# oboard2.net
KiCad netlist of a schematic drawn in EAGLE
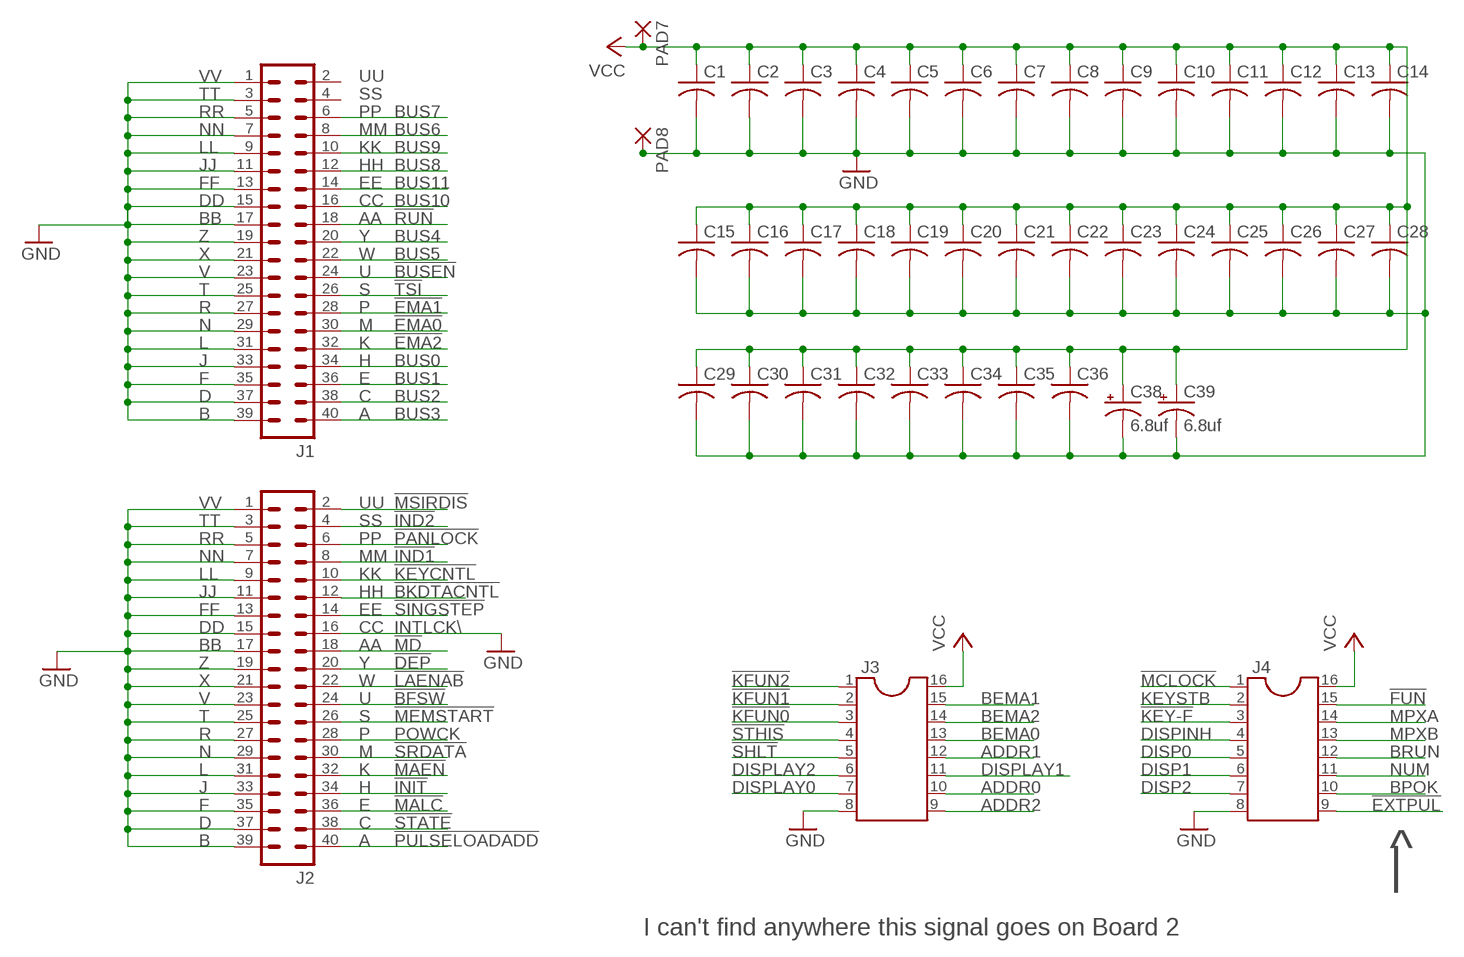
[diagram p0: schematic, sheet 1]
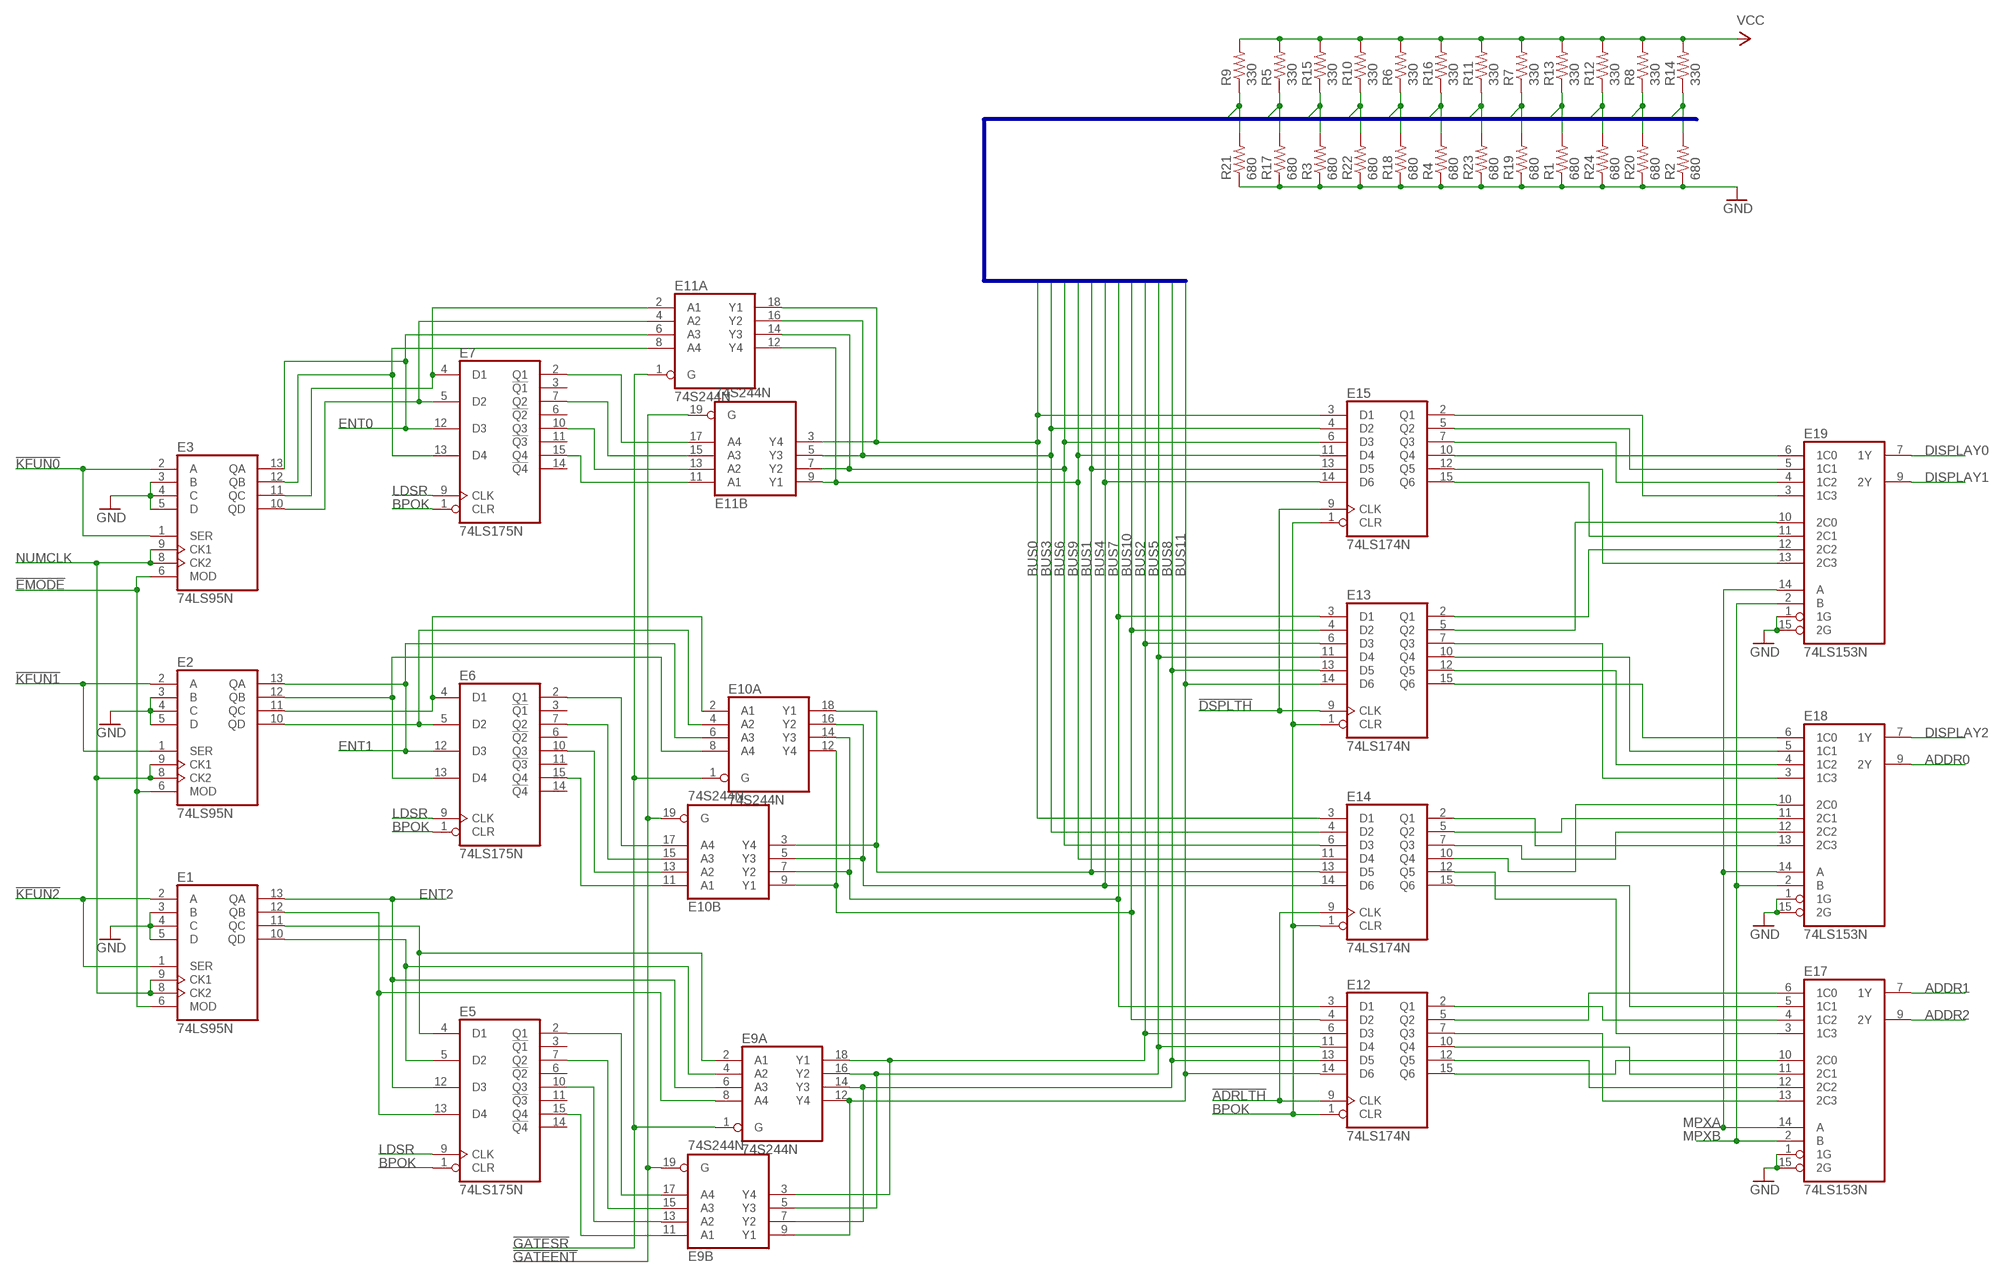
[diagram p1: schematic, sheet 2]
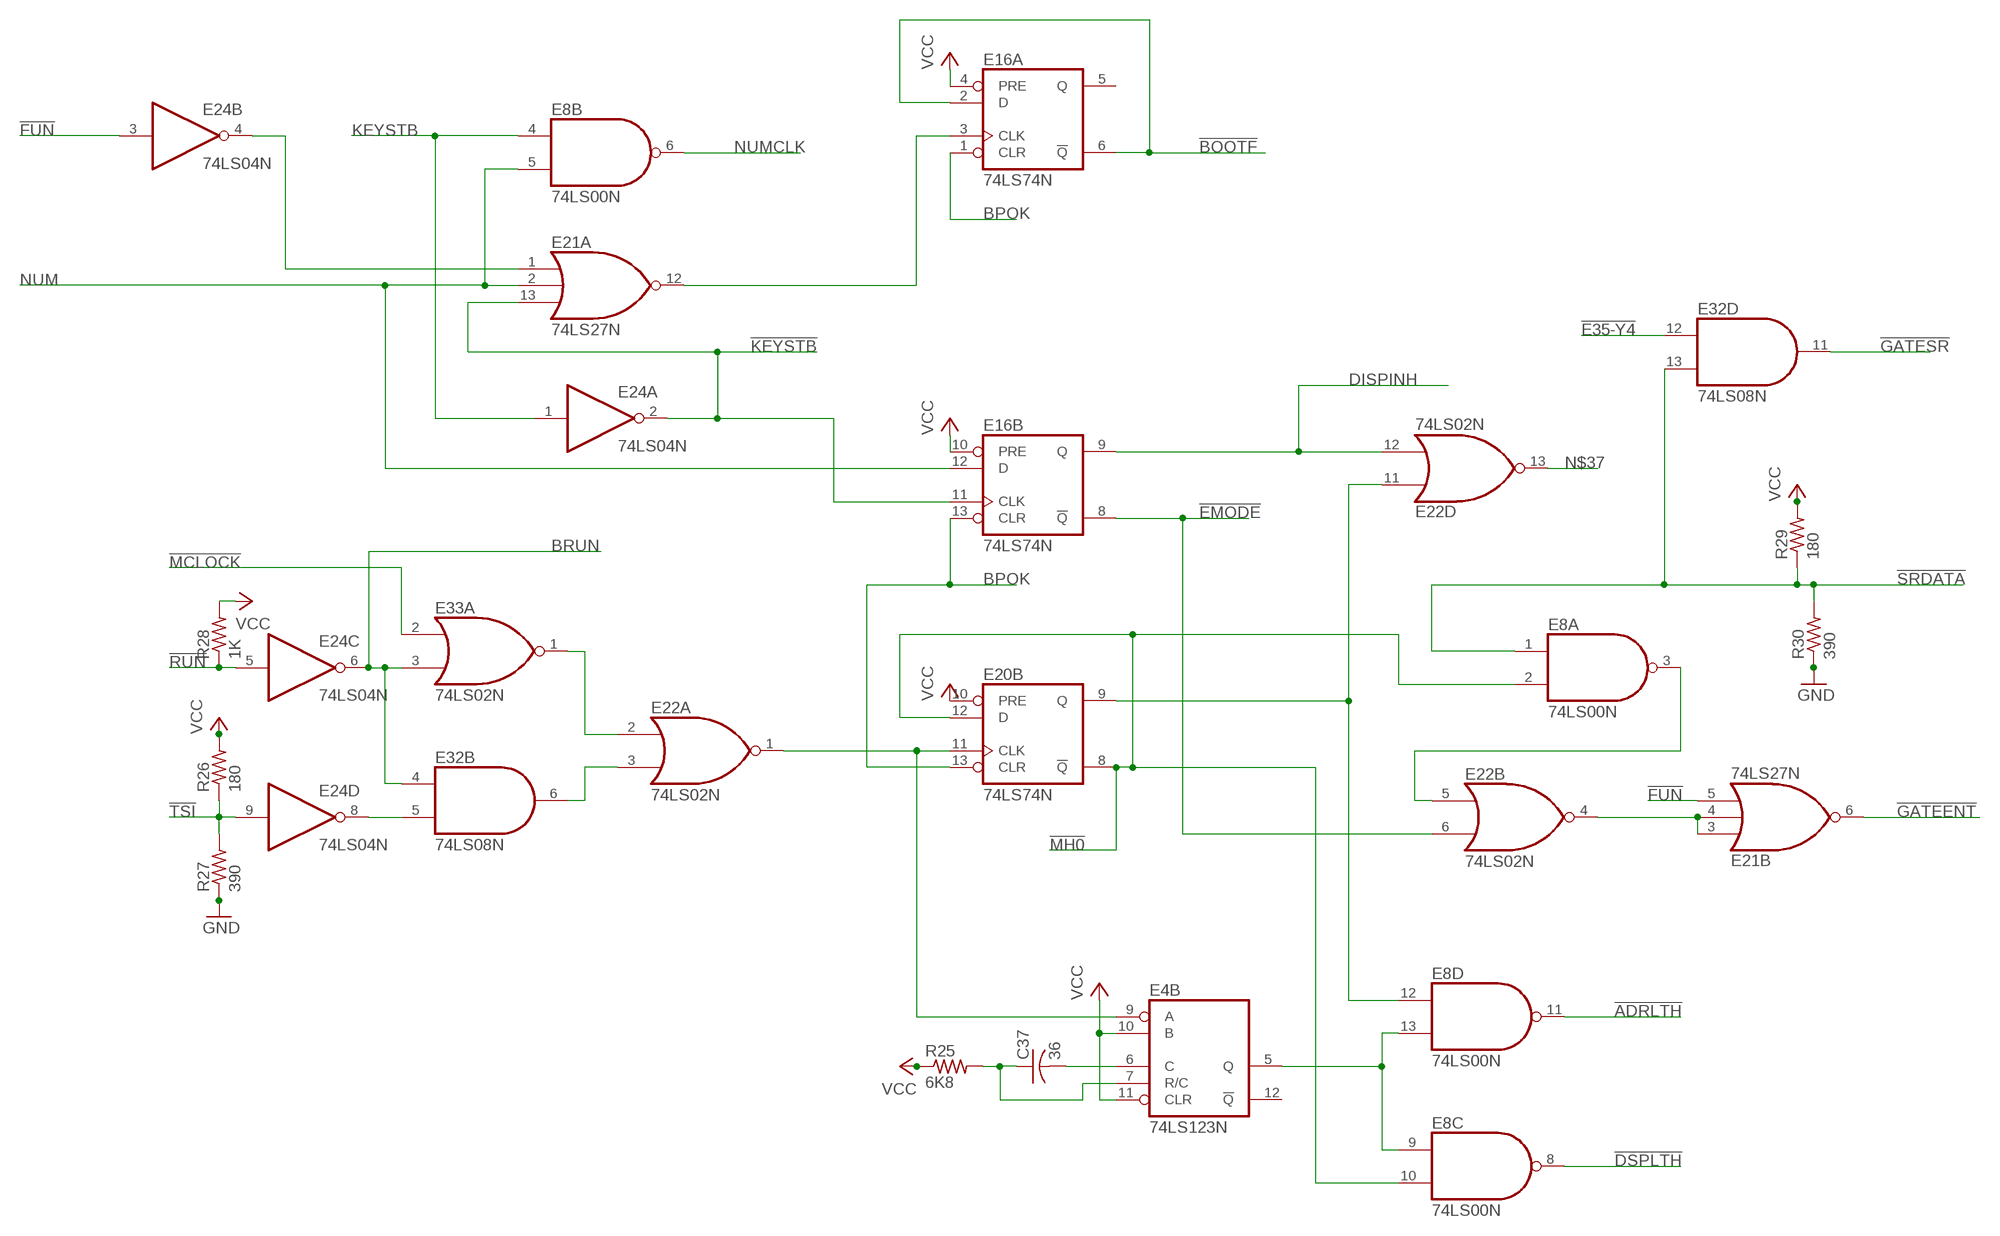
[diagram p2: schematic, sheet 3]
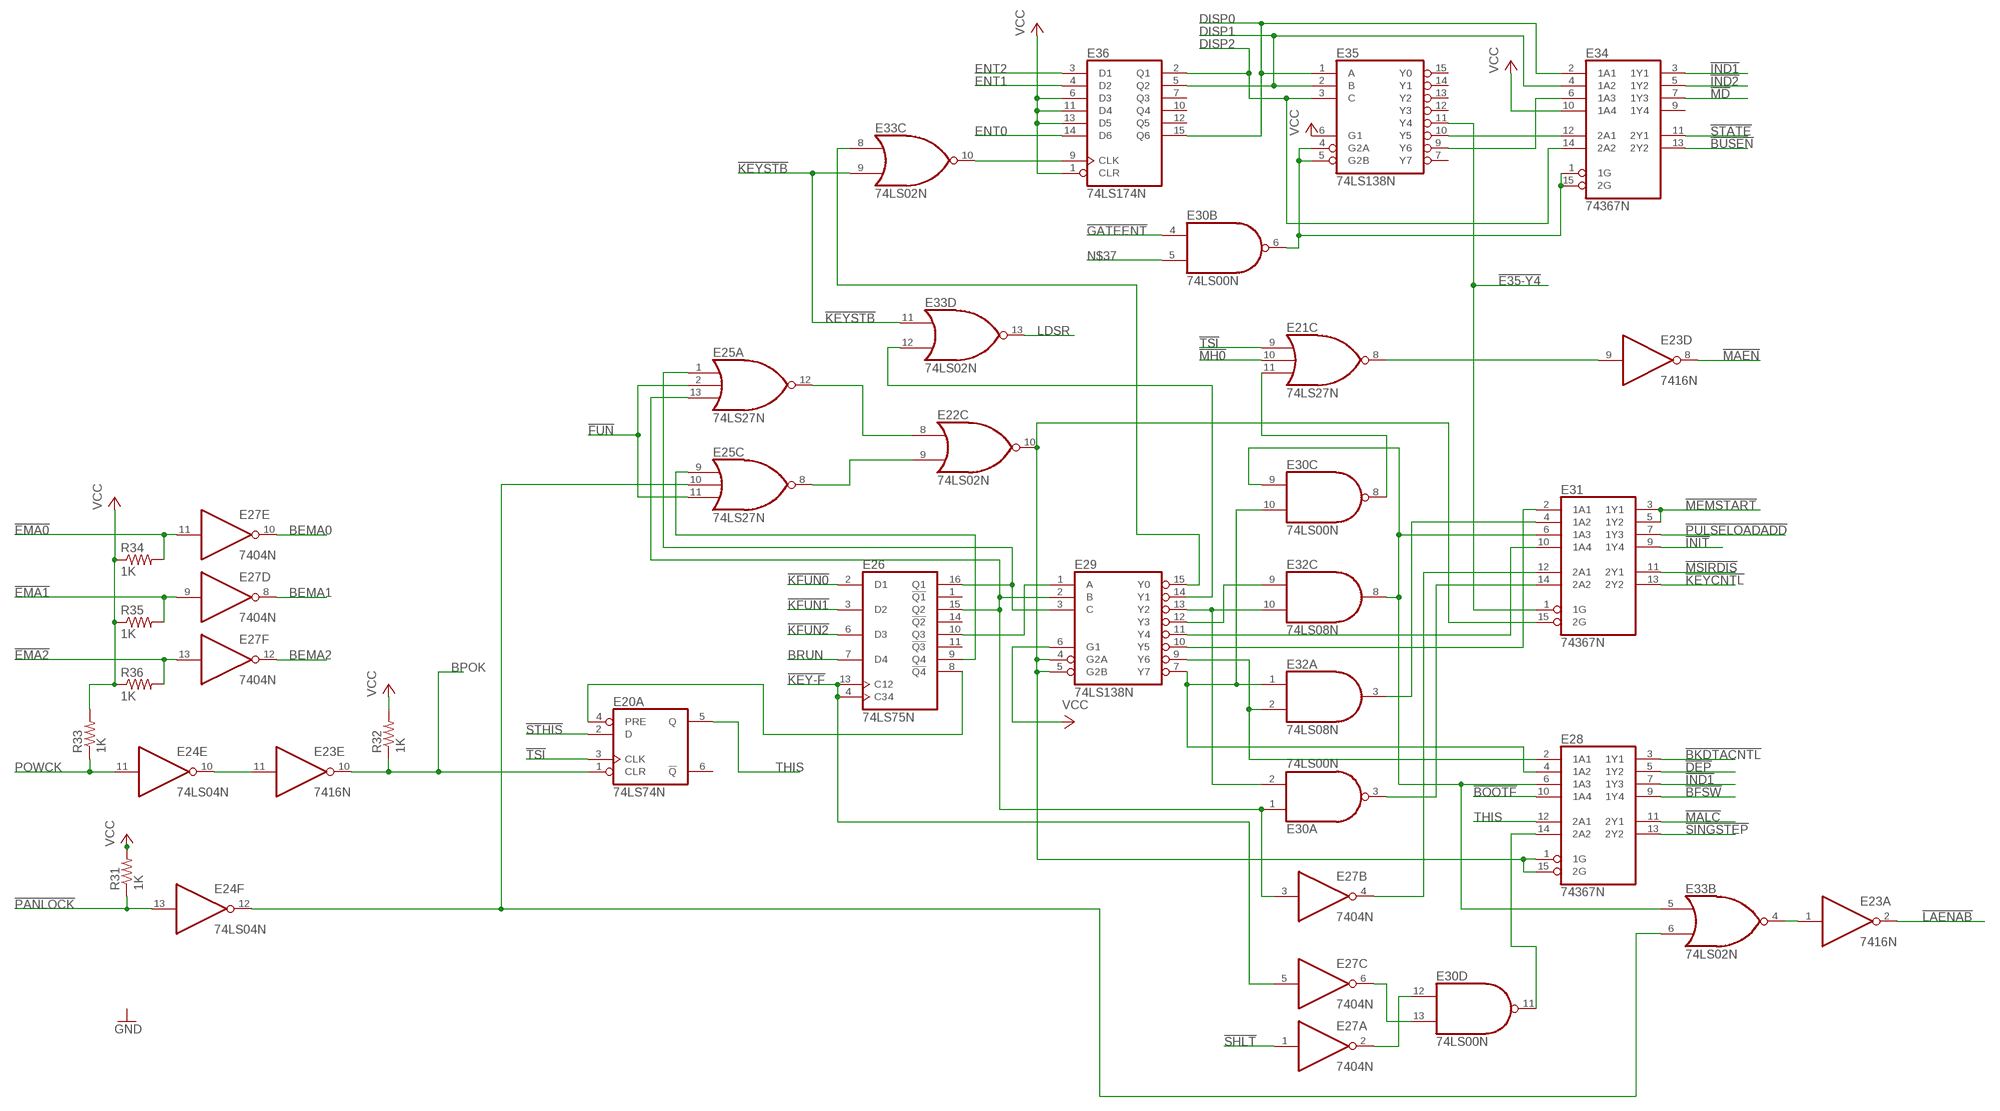
[diagram p3: schematic, sheet 4]

(export (version "E")
  (design (tool "Eeschema 10.0.6"))
  (components
    (comp (ref "E1")
      (value "74LS95N")
      (footprint "eagle-import:DIL14")
      (libsource (lib "eagle-import") (part "7495NLS"))
    )
    (comp (ref "E2")
      (value "74LS95N")
      (footprint "eagle-import:DIL14")
      (libsource (lib "eagle-import") (part "7495NLS"))
    )
    (comp (ref "E3")
      (value "74LS95N")
      (footprint "eagle-import:DIL14")
      (libsource (lib "eagle-import") (part "7495NLS"))
    )
    (comp (ref "E5")
      (value "74LS175N")
      (footprint "eagle-import:DIL16")
      (libsource (lib "eagle-import") (part "74175NLS"))
    )
    (comp (ref "E6")
      (value "74LS175N")
      (footprint "eagle-import:DIL16")
      (libsource (lib "eagle-import") (part "74175NLS"))
    )
    (comp (ref "E7")
      (value "74LS175N")
      (footprint "eagle-import:DIL16")
      (libsource (lib "eagle-import") (part "74175NLS"))
    )
    (comp (ref "E9")
      (value "74S244N")
      (footprint "eagle-import:DIL20")
      (libsource (lib "eagle-import") (part "74244NS"))
    )
    (comp (ref "E10")
      (value "74S244N")
      (footprint "eagle-import:DIL20")
      (libsource (lib "eagle-import") (part "74244NS"))
    )
    (comp (ref "E11")
      (value "74S244N")
      (footprint "eagle-import:DIL20")
      (libsource (lib "eagle-import") (part "74244NS"))
    )
    (comp (ref "E12")
      (value "74LS174N")
      (footprint "eagle-import:DIL16")
      (libsource (lib "eagle-import") (part "74174NLS"))
    )
    (comp (ref "E13")
      (value "74LS174N")
      (footprint "eagle-import:DIL16")
      (libsource (lib "eagle-import") (part "74174NLS"))
    )
    (comp (ref "E14")
      (value "74LS174N")
      (footprint "eagle-import:DIL16")
      (libsource (lib "eagle-import") (part "74174NLS"))
    )
    (comp (ref "E15")
      (value "74LS174N")
      (footprint "eagle-import:DIL16")
      (libsource (lib "eagle-import") (part "74174NLS"))
    )
    (comp (ref "E17")
      (value "74LS153N")
      (footprint "eagle-import:DIL16")
      (libsource (lib "eagle-import") (part "74153NLS"))
    )
    (comp (ref "E18")
      (value "74LS153N")
      (footprint "eagle-import:DIL16")
      (libsource (lib "eagle-import") (part "74153NLS"))
    )
    (comp (ref "E19")
      (value "74LS153N")
      (footprint "eagle-import:DIL16")
      (libsource (lib "eagle-import") (part "74153NLS"))
    )
    (comp (ref "R1")
      (value "680")
      (footprint "eagle-import:0207_10")
      (libsource (lib "eagle-import") (part "R-US_0207/10"))
    )
    (comp (ref "R2")
      (value "680")
      (footprint "eagle-import:0207_10")
      (libsource (lib "eagle-import") (part "R-US_0207/10"))
    )
    (comp (ref "R3")
      (value "680")
      (footprint "eagle-import:0207_10")
      (libsource (lib "eagle-import") (part "R-US_0207/10"))
    )
    (comp (ref "R4")
      (value "680")
      (footprint "eagle-import:0207_10")
      (libsource (lib "eagle-import") (part "R-US_0207/10"))
    )
    (comp (ref "R5")
      (value "330")
      (footprint "eagle-import:0207_10")
      (libsource (lib "eagle-import") (part "R-US_0207/10"))
    )
    (comp (ref "R6")
      (value "330")
      (footprint "eagle-import:0207_10")
      (libsource (lib "eagle-import") (part "R-US_0207/10"))
    )
    (comp (ref "R7")
      (value "330")
      (footprint "eagle-import:0207_10")
      (libsource (lib "eagle-import") (part "R-US_0207/10"))
    )
    (comp (ref "R8")
      (value "330")
      (footprint "eagle-import:0207_10")
      (libsource (lib "eagle-import") (part "R-US_0207/10"))
    )
    (comp (ref "R9")
      (value "330")
      (footprint "eagle-import:0207_10")
      (libsource (lib "eagle-import") (part "R-US_0207/10"))
    )
    (comp (ref "R10")
      (value "330")
      (footprint "eagle-import:0207_10")
      (libsource (lib "eagle-import") (part "R-US_0207/10"))
    )
    (comp (ref "R11")
      (value "330")
      (footprint "eagle-import:0207_10")
      (libsource (lib "eagle-import") (part "R-US_0207/10"))
    )
    (comp (ref "R12")
      (value "330")
      (footprint "eagle-import:0207_10")
      (libsource (lib "eagle-import") (part "R-US_0207/10"))
    )
    (comp (ref "R13")
      (value "330")
      (footprint "eagle-import:0207_10")
      (libsource (lib "eagle-import") (part "R-US_0207/10"))
    )
    (comp (ref "R14")
      (value "330")
      (footprint "eagle-import:0207_10")
      (libsource (lib "eagle-import") (part "R-US_0207/10"))
    )
    (comp (ref "R15")
      (value "330")
      (footprint "eagle-import:0207_10")
      (libsource (lib "eagle-import") (part "R-US_0207/10"))
    )
    (comp (ref "R16")
      (value "330")
      (footprint "eagle-import:0207_10")
      (libsource (lib "eagle-import") (part "R-US_0207/10"))
    )
    (comp (ref "R17")
      (value "680")
      (footprint "eagle-import:0207_10")
      (libsource (lib "eagle-import") (part "R-US_0207/10"))
    )
    (comp (ref "R18")
      (value "680")
      (footprint "eagle-import:0207_10")
      (libsource (lib "eagle-import") (part "R-US_0207/10"))
    )
    (comp (ref "R19")
      (value "680")
      (footprint "eagle-import:0207_10")
      (libsource (lib "eagle-import") (part "R-US_0207/10"))
    )
    (comp (ref "R20")
      (value "680")
      (footprint "eagle-import:0207_10")
      (libsource (lib "eagle-import") (part "R-US_0207/10"))
    )
    (comp (ref "R21")
      (value "680")
      (footprint "eagle-import:0207_10")
      (libsource (lib "eagle-import") (part "R-US_0207/10"))
    )
    (comp (ref "R22")
      (value "680")
      (footprint "eagle-import:0207_10")
      (libsource (lib "eagle-import") (part "R-US_0207/10"))
    )
    (comp (ref "R23")
      (value "680")
      (footprint "eagle-import:0207_10")
      (libsource (lib "eagle-import") (part "R-US_0207/10"))
    )
    (comp (ref "R24")
      (value "680")
      (footprint "eagle-import:0207_10")
      (libsource (lib "eagle-import") (part "R-US_0207/10"))
    )
    (comp (ref "E20")
      (value "74LS74N")
      (footprint "eagle-import:DIL14")
      (libsource (lib "eagle-import") (part "7474NLS"))
    )
    (comp (ref "E21")
      (value "74LS27N")
      (footprint "eagle-import:DIL14")
      (libsource (lib "eagle-import") (part "7427NLS"))
    )
    (comp (ref "E22")
      (value "74LS02N")
      (footprint "eagle-import:DIL14")
      (libsource (lib "eagle-import") (part "7402NLS"))
    )
    (comp (ref "E23")
      (value "7416N")
      (footprint "eagle-import:DIL14")
      (libsource (lib "eagle-import") (part "7416N"))
    )
    (comp (ref "E24")
      (value "74LS04N")
      (footprint "eagle-import:DIL14")
      (libsource (lib "eagle-import") (part "7404NLS"))
    )
    (comp (ref "E25")
      (value "74LS27N")
      (footprint "eagle-import:DIL14")
      (libsource (lib "eagle-import") (part "7427NLS"))
    )
    (comp (ref "E26")
      (value "74LS75N")
      (footprint "eagle-import:DIL16")
      (libsource (lib "eagle-import") (part "7475NLS"))
    )
    (comp (ref "E27")
      (value "7404N")
      (footprint "eagle-import:DIL14")
      (libsource (lib "eagle-import") (part "7404N"))
    )
    (comp (ref "E28")
      (value "74367N")
      (footprint "eagle-import:DIL16")
      (libsource (lib "eagle-import") (part "74367N"))
    )
    (comp (ref "E29")
      (value "74LS138N")
      (footprint "eagle-import:DIL16")
      (libsource (lib "eagle-import") (part "74138NLS"))
    )
    (comp (ref "E30")
      (value "74LS00N")
      (footprint "eagle-import:DIL14")
      (libsource (lib "eagle-import") (part "7400NLS"))
    )
    (comp (ref "E31")
      (value "74367N")
      (footprint "eagle-import:DIL16")
      (libsource (lib "eagle-import") (part "74367N"))
    )
    (comp (ref "E32")
      (value "74LS08N")
      (footprint "eagle-import:DIL14")
      (libsource (lib "eagle-import") (part "7408NLS"))
    )
    (comp (ref "E33")
      (value "74LS02N")
      (footprint "eagle-import:DIL14")
      (libsource (lib "eagle-import") (part "7402NLS"))
    )
    (comp (ref "E34")
      (value "74367N")
      (footprint "eagle-import:DIL16")
      (libsource (lib "eagle-import") (part "74367N"))
    )
    (comp (ref "E35")
      (value "74LS138N")
      (footprint "eagle-import:DIL16")
      (libsource (lib "eagle-import") (part "74138NLS"))
    )
    (comp (ref "E36")
      (value "74LS174N")
      (footprint "eagle-import:DIL16")
      (libsource (lib "eagle-import") (part "74174NLS"))
    )
    (comp (ref "R31")
      (value "1K")
      (footprint "eagle-import:0207_10")
      (libsource (lib "eagle-import") (part "R-US_0207/10"))
    )
    (comp (ref "R32")
      (value "1K")
      (footprint "eagle-import:0207_10")
      (libsource (lib "eagle-import") (part "R-US_0207/10"))
    )
    (comp (ref "R33")
      (value "1K")
      (footprint "eagle-import:0207_10")
      (libsource (lib "eagle-import") (part "R-US_0207/10"))
    )
    (comp (ref "R34")
      (value "1K")
      (footprint "eagle-import:0207_10")
      (libsource (lib "eagle-import") (part "R-US_0207/10"))
    )
    (comp (ref "R35")
      (value "1K")
      (footprint "eagle-import:0207_10")
      (libsource (lib "eagle-import") (part "R-US_0207/10"))
    )
    (comp (ref "R36")
      (value "1K")
      (footprint "eagle-import:0207_10")
      (libsource (lib "eagle-import") (part "R-US_0207/10"))
    )
    (comp (ref "C37")
      (value "36")
      (footprint "eagle-import:C050-025X075")
      (libsource (lib "eagle-import") (part "C-US050-025X075"))
    )
    (comp (ref "E4")
      (value "74LS123N")
      (footprint "eagle-import:DIL16")
      (libsource (lib "eagle-import") (part "74123NLS"))
    )
    (comp (ref "E8")
      (value "74LS00N")
      (footprint "eagle-import:DIL14")
      (libsource (lib "eagle-import") (part "7400NLS"))
    )
    (comp (ref "E16")
      (value "74LS74N")
      (footprint "eagle-import:DIL14")
      (libsource (lib "eagle-import") (part "7474NLS"))
    )
    (comp (ref "R25")
      (value "6K8")
      (footprint "eagle-import:0207_10")
      (libsource (lib "eagle-import") (part "R-US_0207/10"))
    )
    (comp (ref "R26")
      (value "180")
      (footprint "eagle-import:0207_10")
      (libsource (lib "eagle-import") (part "R-US_0207/10"))
    )
    (comp (ref "R27")
      (value "390")
      (footprint "eagle-import:0207_10")
      (libsource (lib "eagle-import") (part "R-US_0207/10"))
    )
    (comp (ref "R28")
      (value "1K")
      (footprint "eagle-import:0207_10")
      (libsource (lib "eagle-import") (part "R-US_0207/10"))
    )
    (comp (ref "R29")
      (value "180")
      (footprint "eagle-import:0207_10")
      (libsource (lib "eagle-import") (part "R-US_0207/10"))
    )
    (comp (ref "R30")
      (value "390")
      (footprint "eagle-import:0207_10")
      (libsource (lib "eagle-import") (part "R-US_0207/10"))
    )
    (comp (ref "C1")
      (value "C-US050-025X075")
      (footprint "eagle-import:C050-025X075")
      (libsource (lib "eagle-import") (part "C-US050-025X075"))
    )
    (comp (ref "C2")
      (value "C-US050-025X075")
      (footprint "eagle-import:C050-025X075")
      (libsource (lib "eagle-import") (part "C-US050-025X075"))
    )
    (comp (ref "C3")
      (value "C-US050-025X075")
      (footprint "eagle-import:C050-025X075")
      (libsource (lib "eagle-import") (part "C-US050-025X075"))
    )
    (comp (ref "C4")
      (value "C-US050-025X075")
      (footprint "eagle-import:C050-025X075")
      (libsource (lib "eagle-import") (part "C-US050-025X075"))
    )
    (comp (ref "C5")
      (value "C-US050-025X075")
      (footprint "eagle-import:C050-025X075")
      (libsource (lib "eagle-import") (part "C-US050-025X075"))
    )
    (comp (ref "C6")
      (value "C-US050-025X075")
      (footprint "eagle-import:C050-025X075")
      (libsource (lib "eagle-import") (part "C-US050-025X075"))
    )
    (comp (ref "C7")
      (value "C-US050-025X075")
      (footprint "eagle-import:C050-025X075")
      (libsource (lib "eagle-import") (part "C-US050-025X075"))
    )
    (comp (ref "C8")
      (value "C-US050-025X075")
      (footprint "eagle-import:C050-025X075")
      (libsource (lib "eagle-import") (part "C-US050-025X075"))
    )
    (comp (ref "C9")
      (value "C-US050-025X075")
      (footprint "eagle-import:C050-025X075")
      (libsource (lib "eagle-import") (part "C-US050-025X075"))
    )
    (comp (ref "C10")
      (value "C-US050-025X075")
      (footprint "eagle-import:C050-025X075")
      (libsource (lib "eagle-import") (part "C-US050-025X075"))
    )
    (comp (ref "C11")
      (value "C-US050-025X075")
      (footprint "eagle-import:C050-025X075")
      (libsource (lib "eagle-import") (part "C-US050-025X075"))
    )
    (comp (ref "C12")
      (value "C-US050-025X075")
      (footprint "eagle-import:C050-025X075")
      (libsource (lib "eagle-import") (part "C-US050-025X075"))
    )
    (comp (ref "C13")
      (value "C-US050-025X075")
      (footprint "eagle-import:C050-025X075")
      (libsource (lib "eagle-import") (part "C-US050-025X075"))
    )
    (comp (ref "C14")
      (value "C-US050-025X075")
      (footprint "eagle-import:C050-025X075")
      (libsource (lib "eagle-import") (part "C-US050-025X075"))
    )
    (comp (ref "C15")
      (value "C-US050-025X075")
      (footprint "eagle-import:C050-025X075")
      (libsource (lib "eagle-import") (part "C-US050-025X075"))
    )
    (comp (ref "C16")
      (value "C-US050-025X075")
      (footprint "eagle-import:C050-025X075")
      (libsource (lib "eagle-import") (part "C-US050-025X075"))
    )
    (comp (ref "C17")
      (value "C-US050-025X075")
      (footprint "eagle-import:C050-025X075")
      (libsource (lib "eagle-import") (part "C-US050-025X075"))
    )
    (comp (ref "C18")
      (value "C-US050-025X075")
      (footprint "eagle-import:C050-025X075")
      (libsource (lib "eagle-import") (part "C-US050-025X075"))
    )
    (comp (ref "C19")
      (value "C-US050-025X075")
      (footprint "eagle-import:C050-025X075")
      (libsource (lib "eagle-import") (part "C-US050-025X075"))
    )
    (comp (ref "C20")
      (value "C-US050-025X075")
      (footprint "eagle-import:C050-025X075")
      (libsource (lib "eagle-import") (part "C-US050-025X075"))
    )
    (comp (ref "C21")
      (value "C-US050-025X075")
      (footprint "eagle-import:C050-025X075")
      (libsource (lib "eagle-import") (part "C-US050-025X075"))
    )
    (comp (ref "C22")
      (value "C-US050-025X075")
      (footprint "eagle-import:C050-025X075")
      (libsource (lib "eagle-import") (part "C-US050-025X075"))
    )
    (comp (ref "C23")
      (value "C-US050-025X075")
      (footprint "eagle-import:C050-025X075")
      (libsource (lib "eagle-import") (part "C-US050-025X075"))
    )
    (comp (ref "C24")
      (value "C-US050-025X075")
      (footprint "eagle-import:C050-025X075")
      (libsource (lib "eagle-import") (part "C-US050-025X075"))
    )
    (comp (ref "C25")
      (value "C-US050-025X075")
      (footprint "eagle-import:C050-025X075")
      (libsource (lib "eagle-import") (part "C-US050-025X075"))
    )
    (comp (ref "C26")
      (value "C-US050-025X075")
      (footprint "eagle-import:C050-025X075")
      (libsource (lib "eagle-import") (part "C-US050-025X075"))
    )
    (comp (ref "C27")
      (value "C-US050-025X075")
      (footprint "eagle-import:C050-025X075")
      (libsource (lib "eagle-import") (part "C-US050-025X075"))
    )
    (comp (ref "C28")
      (value "C-US050-025X075")
      (footprint "eagle-import:C050-025X075")
      (libsource (lib "eagle-import") (part "C-US050-025X075"))
    )
    (comp (ref "C29")
      (value "C-US050-025X075")
      (footprint "eagle-import:C050-025X075")
      (libsource (lib "eagle-import") (part "C-US050-025X075"))
    )
    (comp (ref "C30")
      (value "C-US050-025X075")
      (footprint "eagle-import:C050-025X075")
      (libsource (lib "eagle-import") (part "C-US050-025X075"))
    )
    (comp (ref "C31")
      (value "C-US050-025X075")
      (footprint "eagle-import:C050-025X075")
      (libsource (lib "eagle-import") (part "C-US050-025X075"))
    )
    (comp (ref "C32")
      (value "C-US050-025X075")
      (footprint "eagle-import:C050-025X075")
      (libsource (lib "eagle-import") (part "C-US050-025X075"))
    )
    (comp (ref "C33")
      (value "C-US050-025X075")
      (footprint "eagle-import:C050-025X075")
      (libsource (lib "eagle-import") (part "C-US050-025X075"))
    )
    (comp (ref "C34")
      (value "C-US050-025X075")
      (footprint "eagle-import:C050-025X075")
      (libsource (lib "eagle-import") (part "C-US050-025X075"))
    )
    (comp (ref "C35")
      (value "C-US050-025X075")
      (footprint "eagle-import:C050-025X075")
      (libsource (lib "eagle-import") (part "C-US050-025X075"))
    )
    (comp (ref "C36")
      (value "C-US050-025X075")
      (footprint "eagle-import:C050-025X075")
      (libsource (lib "eagle-import") (part "C-US050-025X075"))
    )
    (comp (ref "C38")
      (value "6.8uf")
      (footprint "eagle-import:E15-5")
      (libsource (lib "eagle-import") (part "CPOL-USE15-5AXIAL"))
    )
    (comp (ref "C39")
      (value "6.8uf")
      (footprint "eagle-import:E15-5")
      (libsource (lib "eagle-import") (part "CPOL-USE15-5AXIAL"))
    )
    (comp (ref "J1")
      (value "40H")
      (footprint "eagle-import:40H")
      (libsource (lib "eagle-import") (part "40H"))
    )
    (comp (ref "J2")
      (value "40H")
      (footprint "eagle-import:40H")
      (libsource (lib "eagle-import") (part "40H"))
    )
    (comp (ref "J3")
      (value "DIL16S")
      (footprint "eagle-import:SOCKET-16")
      (libsource (lib "eagle-import") (part "DIL16S"))
    )
    (comp (ref "J4")
      (value "DIL16S")
      (footprint "eagle-import:SOCKET-16")
      (libsource (lib "eagle-import") (part "DIL16S"))
    )
    (comp (ref "PAD7")
      (value "3,81/1,4")
      (footprint "eagle-import:3,81_1,4")
      (libsource (lib "eagle-import") (part "3,81/1,4"))
    )
    (comp (ref "PAD8")
      (value "3,81/1,4")
      (footprint "eagle-import:3,81_1,4")
      (libsource (lib "eagle-import") (part "3,81/1,4"))
    )
  )
  (nets
    (net (code "1") (name "ADDR0") (class "Default")
      (node (ref "E18") (pin "9") (pinfunction "2Y_9") (pintype "output"))
      (node (ref "J3") (pin "10") (pinfunction "10_10") (pintype "passive"))
    )
    (net (code "2") (name "ADDR1") (class "Default")
      (node (ref "E17") (pin "7") (pinfunction "1Y_7") (pintype "output"))
      (node (ref "J3") (pin "12") (pinfunction "12_12") (pintype "passive"))
    )
    (net (code "3") (name "ADDR2") (class "Default")
      (node (ref "E17") (pin "9") (pinfunction "2Y_9") (pintype "output"))
      (node (ref "J3") (pin "9") (pinfunction "9_9") (pintype "passive"))
    )
    (net (code "4") (name "BEMA0") (class "Default")
      (node (ref "E27") (pin "10") (pinfunction "O_10") (pintype "output"))
      (node (ref "J3") (pin "13") (pinfunction "13_13") (pintype "passive"))
    )
    (net (code "5") (name "BEMA1") (class "Default")
      (node (ref "E27") (pin "8") (pinfunction "O_8") (pintype "output"))
      (node (ref "J3") (pin "15") (pinfunction "15_15") (pintype "passive"))
    )
    (net (code "6") (name "BEMA2") (class "Default")
      (node (ref "E27") (pin "12") (pinfunction "O_12") (pintype "output"))
      (node (ref "J3") (pin "14") (pinfunction "14_14") (pintype "passive"))
    )
    (net (code "7") (name "BPOK") (class "Default")
      (node (ref "E12") (pin "1") (pinfunction "CLR_1") (pintype "input"))
      (node (ref "E13") (pin "1") (pinfunction "CLR_1") (pintype "input"))
      (node (ref "E14") (pin "1") (pinfunction "CLR_1") (pintype "input"))
      (node (ref "E15") (pin "1") (pinfunction "CLR_1") (pintype "input"))
      (node (ref "E16") (pin "1") (pinfunction "CLR_1") (pintype "input"))
      (node (ref "E16") (pin "13") (pinfunction "CLR_13") (pintype "input"))
      (node (ref "E20") (pin "1") (pinfunction "CLR_1") (pintype "input"))
      (node (ref "E20") (pin "13") (pinfunction "CLR_13") (pintype "input"))
      (node (ref "E23") (pin "10") (pinfunction "O_10") (pintype "open_collector"))
      (node (ref "E5") (pin "1") (pinfunction "CLR_1") (pintype "input"))
      (node (ref "E6") (pin "1") (pinfunction "CLR_1") (pintype "input"))
      (node (ref "E7") (pin "1") (pinfunction "CLR_1") (pintype "input"))
      (node (ref "J4") (pin "10") (pinfunction "10_10") (pintype "passive"))
      (node (ref "R32") (pin "1") (pinfunction "1_1") (pintype "passive"))
    )
    (net (code "8") (name "BRUN") (class "Default")
      (node (ref "E24") (pin "6") (pinfunction "O_6") (pintype "output"))
      (node (ref "E26") (pin "7") (pinfunction "D4_7") (pintype "input"))
      (node (ref "E32") (pin "4") (pinfunction "I0_4") (pintype "input"))
      (node (ref "E33") (pin "3") (pinfunction "I1_3") (pintype "input"))
      (node (ref "J4") (pin "12") (pinfunction "12_12") (pintype "passive"))
    )
    (net (code "9") (name "BUS0") (class "Default")
      (node (ref "E11") (pin "18") (pinfunction "Y1_18") (pintype "tri_state"))
      (node (ref "E11") (pin "3") (pinfunction "Y4_3") (pintype "tri_state"))
      (node (ref "E14") (pin "3") (pinfunction "D1_3") (pintype "input"))
      (node (ref "E15") (pin "3") (pinfunction "D1_3") (pintype "input"))
      (node (ref "J1") (pin "34") (pinfunction "34_34") (pintype "passive"))
      (node (ref "R21") (pin "2") (pinfunction "2_2") (pintype "passive"))
      (node (ref "R9") (pin "1") (pinfunction "1_1") (pintype "passive"))
    )
    (net (code "10") (name "BUS1") (class "Default")
      (node (ref "E10") (pin "18") (pinfunction "Y1_18") (pintype "tri_state"))
      (node (ref "E10") (pin "3") (pinfunction "Y4_3") (pintype "tri_state"))
      (node (ref "E14") (pin "13") (pinfunction "D5_13") (pintype "input"))
      (node (ref "E15") (pin "13") (pinfunction "D5_13") (pintype "input"))
      (node (ref "J1") (pin "36") (pinfunction "36_36") (pintype "passive"))
      (node (ref "R17") (pin "2") (pinfunction "2_2") (pintype "passive"))
      (node (ref "R5") (pin "1") (pinfunction "1_1") (pintype "passive"))
    )
    (net (code "11") (name "BUS2") (class "Default")
      (node (ref "E12") (pin "6") (pinfunction "D3_6") (pintype "input"))
      (node (ref "E13") (pin "6") (pinfunction "D3_6") (pintype "input"))
      (node (ref "E9") (pin "18") (pinfunction "Y1_18") (pintype "tri_state"))
      (node (ref "E9") (pin "3") (pinfunction "Y4_3") (pintype "tri_state"))
      (node (ref "J1") (pin "38") (pinfunction "38_38") (pintype "passive"))
      (node (ref "R15") (pin "1") (pinfunction "1_1") (pintype "passive"))
      (node (ref "R3") (pin "2") (pinfunction "2_2") (pintype "passive"))
    )
    (net (code "12") (name "BUS3") (class "Default")
      (node (ref "E11") (pin "16") (pinfunction "Y2_16") (pintype "tri_state"))
      (node (ref "E11") (pin "5") (pinfunction "Y3_5") (pintype "tri_state"))
      (node (ref "E14") (pin "4") (pinfunction "D2_4") (pintype "input"))
      (node (ref "E15") (pin "4") (pinfunction "D2_4") (pintype "input"))
      (node (ref "J1") (pin "40") (pinfunction "40_40") (pintype "passive"))
      (node (ref "R10") (pin "1") (pinfunction "1_1") (pintype "passive"))
      (node (ref "R22") (pin "2") (pinfunction "2_2") (pintype "passive"))
    )
    (net (code "13") (name "BUS4") (class "Default")
      (node (ref "E10") (pin "16") (pinfunction "Y2_16") (pintype "tri_state"))
      (node (ref "E10") (pin "5") (pinfunction "Y3_5") (pintype "tri_state"))
      (node (ref "E14") (pin "14") (pinfunction "D6_14") (pintype "input"))
      (node (ref "E15") (pin "14") (pinfunction "D6_14") (pintype "input"))
      (node (ref "J1") (pin "20") (pinfunction "20_20") (pintype "passive"))
      (node (ref "R18") (pin "2") (pinfunction "2_2") (pintype "passive"))
      (node (ref "R6") (pin "1") (pinfunction "1_1") (pintype "passive"))
    )
    (net (code "14") (name "BUS5") (class "Default")
      (node (ref "E12") (pin "11") (pinfunction "D4_11") (pintype "input"))
      (node (ref "E13") (pin "11") (pinfunction "D4_11") (pintype "input"))
      (node (ref "E9") (pin "16") (pinfunction "Y2_16") (pintype "tri_state"))
      (node (ref "E9") (pin "5") (pinfunction "Y3_5") (pintype "tri_state"))
      (node (ref "J1") (pin "22") (pinfunction "22_22") (pintype "passive"))
      (node (ref "R16") (pin "1") (pinfunction "1_1") (pintype "passive"))
      (node (ref "R4") (pin "2") (pinfunction "2_2") (pintype "passive"))
    )
    (net (code "15") (name "BUS6") (class "Default")
      (node (ref "E11") (pin "14") (pinfunction "Y3_14") (pintype "tri_state"))
      (node (ref "E11") (pin "7") (pinfunction "Y2_7") (pintype "tri_state"))
      (node (ref "E14") (pin "6") (pinfunction "D3_6") (pintype "input"))
      (node (ref "E15") (pin "6") (pinfunction "D3_6") (pintype "input"))
      (node (ref "J1") (pin "8") (pinfunction "8_8") (pintype "passive"))
      (node (ref "R11") (pin "1") (pinfunction "1_1") (pintype "passive"))
      (node (ref "R23") (pin "2") (pinfunction "2_2") (pintype "passive"))
    )
    (net (code "16") (name "BUS7") (class "Default")
      (node (ref "E10") (pin "14") (pinfunction "Y3_14") (pintype "tri_state"))
      (node (ref "E10") (pin "7") (pinfunction "Y2_7") (pintype "tri_state"))
      (node (ref "E12") (pin "3") (pinfunction "D1_3") (pintype "input"))
      (node (ref "E13") (pin "3") (pinfunction "D1_3") (pintype "input"))
      (node (ref "J1") (pin "6") (pinfunction "6_6") (pintype "passive"))
      (node (ref "R19") (pin "2") (pinfunction "2_2") (pintype "passive"))
      (node (ref "R7") (pin "1") (pinfunction "1_1") (pintype "passive"))
    )
    (net (code "17") (name "BUS8") (class "Default")
      (node (ref "E12") (pin "13") (pinfunction "D5_13") (pintype "input"))
      (node (ref "E13") (pin "13") (pinfunction "D5_13") (pintype "input"))
      (node (ref "E9") (pin "14") (pinfunction "Y3_14") (pintype "tri_state"))
      (node (ref "E9") (pin "7") (pinfunction "Y2_7") (pintype "tri_state"))
      (node (ref "J1") (pin "12") (pinfunction "12_12") (pintype "passive"))
      (node (ref "R1") (pin "2") (pinfunction "2_2") (pintype "passive"))
      (node (ref "R12") (pin "1") (pinfunction "1_1") (pintype "passive"))
      (node (ref "R13") (pin "1") (pinfunction "1_1") (pintype "passive"))
      (node (ref "R24") (pin "2") (pinfunction "2_2") (pintype "passive"))
    )
    (net (code "18") (name "BUS9") (class "Default")
      (node (ref "E11") (pin "12") (pinfunction "Y4_12") (pintype "tri_state"))
      (node (ref "E11") (pin "9") (pinfunction "Y1_9") (pintype "tri_state"))
      (node (ref "E14") (pin "11") (pinfunction "D4_11") (pintype "input"))
      (node (ref "E15") (pin "11") (pinfunction "D4_11") (pintype "input"))
      (node (ref "J1") (pin "10") (pinfunction "10_10") (pintype "passive"))
    )
    (net (code "19") (name "BUS10") (class "Default")
      (node (ref "E10") (pin "12") (pinfunction "Y4_12") (pintype "tri_state"))
      (node (ref "E10") (pin "9") (pinfunction "Y1_9") (pintype "tri_state"))
      (node (ref "E12") (pin "4") (pinfunction "D2_4") (pintype "input"))
      (node (ref "E13") (pin "4") (pinfunction "D2_4") (pintype "input"))
      (node (ref "J1") (pin "16") (pinfunction "16_16") (pintype "passive"))
      (node (ref "R20") (pin "2") (pinfunction "2_2") (pintype "passive"))
      (node (ref "R8") (pin "1") (pinfunction "1_1") (pintype "passive"))
    )
    (net (code "20") (name "BUS11") (class "Default")
      (node (ref "E12") (pin "14") (pinfunction "D6_14") (pintype "input"))
      (node (ref "E13") (pin "14") (pinfunction "D6_14") (pintype "input"))
      (node (ref "E9") (pin "12") (pinfunction "Y4_12") (pintype "tri_state"))
      (node (ref "E9") (pin "9") (pinfunction "Y1_9") (pintype "tri_state"))
      (node (ref "J1") (pin "14") (pinfunction "14_14") (pintype "passive"))
      (node (ref "R14") (pin "1") (pinfunction "1_1") (pintype "passive"))
      (node (ref "R2") (pin "2") (pinfunction "2_2") (pintype "passive"))
    )
    (net (code "21") (name "DISP0") (class "Default")
      (node (ref "E34") (pin "2") (pinfunction "1A1_2") (pintype "input"))
      (node (ref "E35") (pin "1") (pinfunction "A_1") (pintype "input"))
      (node (ref "E36") (pin "15") (pinfunction "Q6_15") (pintype "output"))
      (node (ref "J4") (pin "5") (pinfunction "5_5") (pintype "passive"))
    )
    (net (code "22") (name "DISP1") (class "Default")
      (node (ref "E34") (pin "4") (pinfunction "1A2_4") (pintype "input"))
      (node (ref "E35") (pin "2") (pinfunction "B_2") (pintype "input"))
      (node (ref "E36") (pin "5") (pinfunction "Q2_5") (pintype "output"))
      (node (ref "J4") (pin "6") (pinfunction "6_6") (pintype "passive"))
    )
    (net (code "23") (name "DISP2") (class "Default")
      (node (ref "E34") (pin "14") (pinfunction "2A2_14") (pintype "input"))
      (node (ref "E35") (pin "3") (pinfunction "C_3") (pintype "input"))
      (node (ref "E36") (pin "2") (pinfunction "Q1_2") (pintype "output"))
      (node (ref "J4") (pin "7") (pinfunction "7_7") (pintype "passive"))
    )
    (net (code "24") (name "DISPINH") (class "Default")
      (node (ref "E16") (pin "9") (pinfunction "Q_9") (pintype "output"))
      (node (ref "E22") (pin "12") (pinfunction "I1_12") (pintype "input"))
      (node (ref "J4") (pin "4") (pinfunction "4_4") (pintype "passive"))
    )
    (net (code "25") (name "DISPLAY0") (class "Default")
      (node (ref "E19") (pin "7") (pinfunction "1Y_7") (pintype "output"))
      (node (ref "J3") (pin "7") (pinfunction "7_7") (pintype "passive"))
    )
    (net (code "26") (name "DISPLAY1") (class "Default")
      (node (ref "E19") (pin "9") (pinfunction "2Y_9") (pintype "output"))
      (node (ref "J3") (pin "11") (pinfunction "11_11") (pintype "passive"))
    )
    (net (code "27") (name "DISPLAY2") (class "Default")
      (node (ref "E18") (pin "7") (pinfunction "1Y_7") (pintype "output"))
      (node (ref "J3") (pin "6") (pinfunction "6_6") (pintype "passive"))
    )
    (net (code "28") (name "ENT0") (class "Default")
      (node (ref "E11") (pin "6") (pinfunction "A3_6") (pintype "input"))
      (node (ref "E3") (pin "13") (pinfunction "QA_13") (pintype "output"))
      (node (ref "E36") (pin "14") (pinfunction "D6_14") (pintype "input"))
      (node (ref "E7") (pin "12") (pinfunction "D3_12") (pintype "input"))
    )
    (net (code "29") (name "ENT1") (class "Default")
      (node (ref "E10") (pin "6") (pinfunction "A3_6") (pintype "input"))
      (node (ref "E2") (pin "13") (pinfunction "QA_13") (pintype "output"))
      (node (ref "E36") (pin "4") (pinfunction "D2_4") (pintype "input"))
      (node (ref "E6") (pin "12") (pinfunction "D3_12") (pintype "input"))
    )
    (net (code "30") (name "ENT2") (class "Default")
      (node (ref "E1") (pin "13") (pinfunction "QA_13") (pintype "output"))
      (node (ref "E36") (pin "3") (pinfunction "D1_3") (pintype "input"))
      (node (ref "E5") (pin "12") (pinfunction "D3_12") (pintype "input"))
      (node (ref "E9") (pin "6") (pinfunction "A3_6") (pintype "input"))
    )
    (net (code "31") (name "GND") (class "Default")
      (node (ref "C1") (pin "2") (pinfunction "2_2") (pintype "passive"))
      (node (ref "C10") (pin "2") (pinfunction "2_2") (pintype "passive"))
      (node (ref "C11") (pin "2") (pinfunction "2_2") (pintype "passive"))
      (node (ref "C12") (pin "2") (pinfunction "2_2") (pintype "passive"))
      (node (ref "C13") (pin "2") (pinfunction "2_2") (pintype "passive"))
      (node (ref "C14") (pin "2") (pinfunction "2_2") (pintype "passive"))
      (node (ref "C15") (pin "2") (pinfunction "2_2") (pintype "passive"))
      (node (ref "C16") (pin "2") (pinfunction "2_2") (pintype "passive"))
      (node (ref "C17") (pin "2") (pinfunction "2_2") (pintype "passive"))
      (node (ref "C18") (pin "2") (pinfunction "2_2") (pintype "passive"))
      (node (ref "C19") (pin "2") (pinfunction "2_2") (pintype "passive"))
      (node (ref "C2") (pin "2") (pinfunction "2_2") (pintype "passive"))
      (node (ref "C20") (pin "2") (pinfunction "2_2") (pintype "passive"))
      (node (ref "C21") (pin "2") (pinfunction "2_2") (pintype "passive"))
      (node (ref "C22") (pin "2") (pinfunction "2_2") (pintype "passive"))
      (node (ref "C23") (pin "2") (pinfunction "2_2") (pintype "passive"))
      (node (ref "C24") (pin "2") (pinfunction "2_2") (pintype "passive"))
      (node (ref "C25") (pin "2") (pinfunction "2_2") (pintype "passive"))
      (node (ref "C26") (pin "2") (pinfunction "2_2") (pintype "passive"))
      (node (ref "C27") (pin "2") (pinfunction "2_2") (pintype "passive"))
      (node (ref "C28") (pin "2") (pinfunction "2_2") (pintype "passive"))
      (node (ref "C29") (pin "2") (pinfunction "2_2") (pintype "passive"))
      (node (ref "C3") (pin "2") (pinfunction "2_2") (pintype "passive"))
      (node (ref "C30") (pin "2") (pinfunction "2_2") (pintype "passive"))
      (node (ref "C31") (pin "2") (pinfunction "2_2") (pintype "passive"))
      (node (ref "C32") (pin "2") (pinfunction "2_2") (pintype "passive"))
      (node (ref "C33") (pin "2") (pinfunction "2_2") (pintype "passive"))
      (node (ref "C34") (pin "2") (pinfunction "2_2") (pintype "passive"))
      (node (ref "C35") (pin "2") (pinfunction "2_2") (pintype "passive"))
      (node (ref "C36") (pin "2") (pinfunction "2_2") (pintype "passive"))
      (node (ref "C38") (pin "-") (pinfunction "-_-") (pintype "passive"))
      (node (ref "C39") (pin "-") (pinfunction "-_-") (pintype "passive"))
      (node (ref "C4") (pin "2") (pinfunction "2_2") (pintype "passive"))
      (node (ref "C5") (pin "2") (pinfunction "2_2") (pintype "passive"))
      (node (ref "C6") (pin "2") (pinfunction "2_2") (pintype "passive"))
      (node (ref "C7") (pin "2") (pinfunction "2_2") (pintype "passive"))
      (node (ref "C8") (pin "2") (pinfunction "2_2") (pintype "passive"))
      (node (ref "C9") (pin "2") (pinfunction "2_2") (pintype "passive"))
      (node (ref "E1") (pin "3") (pinfunction "B_3") (pintype "input"))
      (node (ref "E1") (pin "4") (pinfunction "C_4") (pintype "input"))
      (node (ref "E1") (pin "5") (pinfunction "D_5") (pintype "input"))
      (node (ref "E17") (pin "1") (pinfunction "1G_1") (pintype "input"))
      (node (ref "E17") (pin "15") (pinfunction "2G_15") (pintype "input"))
      (node (ref "E18") (pin "1") (pinfunction "1G_1") (pintype "input"))
      (node (ref "E18") (pin "15") (pinfunction "2G_15") (pintype "input"))
      (node (ref "E19") (pin "1") (pinfunction "1G_1") (pintype "input"))
      (node (ref "E19") (pin "15") (pinfunction "2G_15") (pintype "input"))
      (node (ref "E2") (pin "3") (pinfunction "B_3") (pintype "input"))
      (node (ref "E2") (pin "4") (pinfunction "C_4") (pintype "input"))
      (node (ref "E2") (pin "5") (pinfunction "D_5") (pintype "input"))
      (node (ref "E3") (pin "3") (pinfunction "B_3") (pintype "input"))
      (node (ref "E3") (pin "4") (pinfunction "C_4") (pintype "input"))
      (node (ref "E3") (pin "5") (pinfunction "D_5") (pintype "input"))
      (node (ref "J1") (pin "1") (pinfunction "1_1") (pintype "passive"))
      (node (ref "J1") (pin "11") (pinfunction "11_11") (pintype "passive"))
      (node (ref "J1") (pin "13") (pinfunction "13_13") (pintype "passive"))
      (node (ref "J1") (pin "15") (pinfunction "15_15") (pintype "passive"))
      (node (ref "J1") (pin "17") (pinfunction "17_17") (pintype "passive"))
      (node (ref "J1") (pin "19") (pinfunction "19_19") (pintype "passive"))
      (node (ref "J1") (pin "21") (pinfunction "21_21") (pintype "passive"))
      (node (ref "J1") (pin "23") (pinfunction "23_23") (pintype "passive"))
      (node (ref "J1") (pin "25") (pinfunction "25_25") (pintype "passive"))
      (node (ref "J1") (pin "27") (pinfunction "27_27") (pintype "passive"))
      (node (ref "J1") (pin "29") (pinfunction "29_29") (pintype "passive"))
      (node (ref "J1") (pin "3") (pinfunction "3_3") (pintype "passive"))
      (node (ref "J1") (pin "31") (pinfunction "31_31") (pintype "passive"))
      (node (ref "J1") (pin "33") (pinfunction "33_33") (pintype "passive"))
      (node (ref "J1") (pin "35") (pinfunction "35_35") (pintype "passive"))
      (node (ref "J1") (pin "37") (pinfunction "37_37") (pintype "passive"))
      (node (ref "J1") (pin "39") (pinfunction "39_39") (pintype "passive"))
      (node (ref "J1") (pin "5") (pinfunction "5_5") (pintype "passive"))
      (node (ref "J1") (pin "7") (pinfunction "7_7") (pintype "passive"))
      (node (ref "J1") (pin "9") (pinfunction "9_9") (pintype "passive"))
      (node (ref "J2") (pin "1") (pinfunction "1_1") (pintype "passive"))
      (node (ref "J2") (pin "11") (pinfunction "11_11") (pintype "passive"))
      (node (ref "J2") (pin "13") (pinfunction "13_13") (pintype "passive"))
      (node (ref "J2") (pin "15") (pinfunction "15_15") (pintype "passive"))
      (node (ref "J2") (pin "16") (pinfunction "16_16") (pintype "passive"))
      (node (ref "J2") (pin "17") (pinfunction "17_17") (pintype "passive"))
      (node (ref "J2") (pin "19") (pinfunction "19_19") (pintype "passive"))
      (node (ref "J2") (pin "21") (pinfunction "21_21") (pintype "passive"))
      (node (ref "J2") (pin "23") (pinfunction "23_23") (pintype "passive"))
      (node (ref "J2") (pin "25") (pinfunction "25_25") (pintype "passive"))
      (node (ref "J2") (pin "27") (pinfunction "27_27") (pintype "passive"))
      (node (ref "J2") (pin "29") (pinfunction "29_29") (pintype "passive"))
      (node (ref "J2") (pin "3") (pinfunction "3_3") (pintype "passive"))
      (node (ref "J2") (pin "31") (pinfunction "31_31") (pintype "passive"))
      (node (ref "J2") (pin "33") (pinfunction "33_33") (pintype "passive"))
      (node (ref "J2") (pin "35") (pinfunction "35_35") (pintype "passive"))
      (node (ref "J2") (pin "37") (pinfunction "37_37") (pintype "passive"))
      (node (ref "J2") (pin "39") (pinfunction "39_39") (pintype "passive"))
      (node (ref "J2") (pin "5") (pinfunction "5_5") (pintype "passive"))
      (node (ref "J2") (pin "7") (pinfunction "7_7") (pintype "passive"))
      (node (ref "J2") (pin "9") (pinfunction "9_9") (pintype "passive"))
      (node (ref "J3") (pin "8") (pinfunction "8_8") (pintype "passive"))
      (node (ref "J4") (pin "8") (pinfunction "8_8") (pintype "passive"))
      (node (ref "PAD8") (pin "1") (pinfunction "P_1") (pintype "passive"))
      (node (ref "R1") (pin "1") (pinfunction "1_1") (pintype "passive"))
      (node (ref "R17") (pin "1") (pinfunction "1_1") (pintype "passive"))
      (node (ref "R18") (pin "1") (pinfunction "1_1") (pintype "passive"))
      (node (ref "R19") (pin "1") (pinfunction "1_1") (pintype "passive"))
      (node (ref "R2") (pin "1") (pinfunction "1_1") (pintype "passive"))
      (node (ref "R20") (pin "1") (pinfunction "1_1") (pintype "passive"))
      (node (ref "R21") (pin "1") (pinfunction "1_1") (pintype "passive"))
      (node (ref "R22") (pin "1") (pinfunction "1_1") (pintype "passive"))
      (node (ref "R23") (pin "1") (pinfunction "1_1") (pintype "passive"))
      (node (ref "R24") (pin "1") (pinfunction "1_1") (pintype "passive"))
      (node (ref "R27") (pin "1") (pinfunction "1_1") (pintype "passive"))
      (node (ref "R3") (pin "1") (pinfunction "1_1") (pintype "passive"))
      (node (ref "R30") (pin "1") (pinfunction "1_1") (pintype "passive"))
      (node (ref "R4") (pin "1") (pinfunction "1_1") (pintype "passive"))
    )
    (net (code "32") (name "KEYSTB") (class "Default")
      (node (ref "E24") (pin "1") (pinfunction "I_1") (pintype "input"))
      (node (ref "E8") (pin "4") (pinfunction "I0_4") (pintype "input"))
      (node (ref "J4") (pin "2") (pinfunction "2_2") (pintype "passive"))
    )
    (net (code "33") (name "LDSR") (class "Default")
      (node (ref "E33") (pin "13") (pinfunction "O_13") (pintype "output"))
      (node (ref "E5") (pin "9") (pinfunction "CLK_9") (pintype "input"))
      (node (ref "E6") (pin "9") (pinfunction "CLK_9") (pintype "input"))
      (node (ref "E7") (pin "9") (pinfunction "CLK_9") (pintype "input"))
    )
    (net (code "34") (name "MPXA") (class "Default")
      (node (ref "E17") (pin "14") (pinfunction "A_14") (pintype "input"))
      (node (ref "E18") (pin "14") (pinfunction "A_14") (pintype "input"))
      (node (ref "E19") (pin "14") (pinfunction "A_14") (pintype "input"))
      (node (ref "J4") (pin "14") (pinfunction "14_14") (pintype "passive"))
    )
    (net (code "35") (name "MPXB") (class "Default")
      (node (ref "E17") (pin "2") (pinfunction "B_2") (pintype "input"))
      (node (ref "E18") (pin "2") (pinfunction "B_2") (pintype "input"))
      (node (ref "E19") (pin "2") (pinfunction "B_2") (pintype "input"))
      (node (ref "J4") (pin "13") (pinfunction "13_13") (pintype "passive"))
    )
    (net (code "36") (name "N$37") (class "Default")
      (node (ref "E22") (pin "13") (pinfunction "O_13") (pintype "output"))
      (node (ref "E30") (pin "5") (pinfunction "I1_5") (pintype "input"))
    )
    (net (code "37") (name "NUM") (class "Default")
      (node (ref "E16") (pin "12") (pinfunction "D_12") (pintype "input"))
      (node (ref "E21") (pin "2") (pinfunction "I1_2") (pintype "input"))
      (node (ref "E8") (pin "5") (pinfunction "I1_5") (pintype "input"))
      (node (ref "J4") (pin "11") (pinfunction "11_11") (pintype "passive"))
    )
    (net (code "38") (name "NUMCLK") (class "Default")
      (node (ref "E1") (pin "8") (pinfunction "CK2_8") (pintype "input"))
      (node (ref "E1") (pin "9") (pinfunction "CK1_9") (pintype "input"))
      (node (ref "E2") (pin "8") (pinfunction "CK2_8") (pintype "input"))
      (node (ref "E2") (pin "9") (pinfunction "CK1_9") (pintype "input"))
      (node (ref "E3") (pin "8") (pinfunction "CK2_8") (pintype "input"))
      (node (ref "E3") (pin "9") (pinfunction "CK1_9") (pintype "input"))
      (node (ref "E8") (pin "6") (pinfunction "O_6") (pintype "output"))
    )
    (net (code "39") (name "Net-(E1A-QB)") (class "Default")
      (node (ref "E1") (pin "12") (pinfunction "QB_12") (pintype "output"))
      (node (ref "E5") (pin "13") (pinfunction "D4_13") (pintype "input"))
      (node (ref "E9") (pin "8") (pinfunction "A4_8") (pintype "input"))
    )
    (net (code "40") (name "Net-(E1A-QC)") (class "Default")
      (node (ref "E1") (pin "11") (pinfunction "QC_11") (pintype "output"))
      (node (ref "E5") (pin "4") (pinfunction "D1_4") (pintype "input"))
      (node (ref "E9") (pin "2") (pinfunction "A1_2") (pintype "input"))
    )
    (net (code "41") (name "Net-(E1A-QD)") (class "Default")
      (node (ref "E1") (pin "10") (pinfunction "QD_10") (pintype "output"))
      (node (ref "E5") (pin "5") (pinfunction "D2_5") (pintype "input"))
      (node (ref "E9") (pin "4") (pinfunction "A2_4") (pintype "input"))
    )
    (net (code "42") (name "Net-(E4B-C)") (class "Default")
      (node (ref "C37") (pin "2") (pinfunction "2_2") (pintype "passive"))
      (node (ref "E4") (pin "6") (pinfunction "C_6") (pintype "input"))
    )
    (net (code "43") (name "Net-(E4B-Q)") (class "Default")
      (node (ref "E4") (pin "5") (pinfunction "Q_5") (pintype "output"))
      (node (ref "E8") (pin "13") (pinfunction "I1_13") (pintype "input"))
      (node (ref "E8") (pin "9") (pinfunction "I0_9") (pintype "input"))
    )
    (net (code "44") (name "Net-(E4B-R{slash}C)") (class "Default")
      (node (ref "C37") (pin "1") (pinfunction "1_1") (pintype "passive"))
      (node (ref "E4") (pin "7") (pinfunction "R/C_7") (pintype "input"))
      (node (ref "R25") (pin "2") (pinfunction "2_2") (pintype "passive"))
    )
    (net (code "45") (name "Net-(E5A-Q1)") (class "Default")
      (node (ref "E5") (pin "2") (pinfunction "Q1_2") (pintype "output"))
      (node (ref "E9") (pin "17") (pinfunction "A4_17") (pintype "input"))
    )
    (net (code "46") (name "Net-(E5A-Q2)") (class "Default")
      (node (ref "E5") (pin "7") (pinfunction "Q2_7") (pintype "output"))
      (node (ref "E9") (pin "15") (pinfunction "A3_15") (pintype "input"))
    )
    (net (code "47") (name "Net-(E5A-Q3)") (class "Default")
      (node (ref "E5") (pin "10") (pinfunction "Q3_10") (pintype "output"))
      (node (ref "E9") (pin "13") (pinfunction "A2_13") (pintype "input"))
    )
    (net (code "48") (name "Net-(E5A-Q4)") (class "Default")
      (node (ref "E5") (pin "15") (pinfunction "Q4_15") (pintype "output"))
      (node (ref "E9") (pin "11") (pinfunction "A1_11") (pintype "input"))
    )
    (net (code "49") (name "Net-(E10A-A1)") (class "Default")
      (node (ref "E10") (pin "2") (pinfunction "A1_2") (pintype "input"))
      (node (ref "E2") (pin "11") (pinfunction "QC_11") (pintype "output"))
      (node (ref "E6") (pin "4") (pinfunction "D1_4") (pintype "input"))
    )
    (net (code "50") (name "Net-(E10A-A2)") (class "Default")
      (node (ref "E10") (pin "4") (pinfunction "A2_4") (pintype "input"))
      (node (ref "E2") (pin "10") (pinfunction "QD_10") (pintype "output"))
      (node (ref "E6") (pin "5") (pinfunction "D2_5") (pintype "input"))
    )
    (net (code "51") (name "Net-(E10A-A4)") (class "Default")
      (node (ref "E10") (pin "8") (pinfunction "A4_8") (pintype "input"))
      (node (ref "E2") (pin "12") (pinfunction "QB_12") (pintype "output"))
      (node (ref "E6") (pin "13") (pinfunction "D4_13") (pintype "input"))
    )
    (net (code "52") (name "Net-(E10B-A1)") (class "Default")
      (node (ref "E10") (pin "11") (pinfunction "A1_11") (pintype "input"))
      (node (ref "E6") (pin "15") (pinfunction "Q4_15") (pintype "output"))
    )
    (net (code "53") (name "Net-(E10B-A2)") (class "Default")
      (node (ref "E10") (pin "13") (pinfunction "A2_13") (pintype "input"))
      (node (ref "E6") (pin "10") (pinfunction "Q3_10") (pintype "output"))
    )
    (net (code "54") (name "Net-(E10B-A3)") (class "Default")
      (node (ref "E10") (pin "15") (pinfunction "A3_15") (pintype "input"))
      (node (ref "E6") (pin "7") (pinfunction "Q2_7") (pintype "output"))
    )
    (net (code "55") (name "Net-(E10B-A4)") (class "Default")
      (node (ref "E10") (pin "17") (pinfunction "A4_17") (pintype "input"))
      (node (ref "E6") (pin "2") (pinfunction "Q1_2") (pintype "output"))
    )
    (net (code "56") (name "Net-(E11A-A1)") (class "Default")
      (node (ref "E11") (pin "2") (pinfunction "A1_2") (pintype "input"))
      (node (ref "E3") (pin "11") (pinfunction "QC_11") (pintype "output"))
      (node (ref "E7") (pin "4") (pinfunction "D1_4") (pintype "input"))
    )
    (net (code "57") (name "Net-(E11A-A2)") (class "Default")
      (node (ref "E11") (pin "4") (pinfunction "A2_4") (pintype "input"))
      (node (ref "E3") (pin "10") (pinfunction "QD_10") (pintype "output"))
      (node (ref "E7") (pin "5") (pinfunction "D2_5") (pintype "input"))
    )
    (net (code "58") (name "Net-(E11A-A4)") (class "Default")
      (node (ref "E11") (pin "8") (pinfunction "A4_8") (pintype "input"))
      (node (ref "E3") (pin "12") (pinfunction "QB_12") (pintype "output"))
      (node (ref "E7") (pin "13") (pinfunction "D4_13") (pintype "input"))
    )
    (net (code "59") (name "Net-(E11B-A1)") (class "Default")
      (node (ref "E11") (pin "11") (pinfunction "A1_11") (pintype "input"))
      (node (ref "E7") (pin "15") (pinfunction "Q4_15") (pintype "output"))
    )
    (net (code "60") (name "Net-(E11B-A2)") (class "Default")
      (node (ref "E11") (pin "13") (pinfunction "A2_13") (pintype "input"))
      (node (ref "E7") (pin "10") (pinfunction "Q3_10") (pintype "output"))
    )
    (net (code "61") (name "Net-(E11B-A3)") (class "Default")
      (node (ref "E11") (pin "15") (pinfunction "A3_15") (pintype "input"))
      (node (ref "E7") (pin "7") (pinfunction "Q2_7") (pintype "output"))
    )
    (net (code "62") (name "Net-(E11B-A4)") (class "Default")
      (node (ref "E11") (pin "17") (pinfunction "A4_17") (pintype "input"))
      (node (ref "E7") (pin "2") (pinfunction "Q1_2") (pintype "output"))
    )
    (net (code "63") (name "Net-(E12A-Q1)") (class "Default")
      (node (ref "E12") (pin "2") (pinfunction "Q1_2") (pintype "output"))
      (node (ref "E17") (pin "4") (pinfunction "1C2_4") (pintype "input"))
    )
    (net (code "64") (name "Net-(E12A-Q2)") (class "Default")
      (node (ref "E12") (pin "5") (pinfunction "Q2_5") (pintype "output"))
      (node (ref "E17") (pin "6") (pinfunction "1C0_6") (pintype "input"))
    )
    (net (code "65") (name "Net-(E12A-Q3)") (class "Default")
      (node (ref "E12") (pin "7") (pinfunction "Q3_7") (pintype "output"))
      (node (ref "E17") (pin "13") (pinfunction "2C3_13") (pintype "input"))
    )
    (net (code "66") (name "Net-(E12A-Q4)") (class "Default")
      (node (ref "E12") (pin "10") (pinfunction "Q4_10") (pintype "output"))
      (node (ref "E17") (pin "11") (pinfunction "2C1_11") (pintype "input"))
    )
    (net (code "67") (name "Net-(E12A-Q5)") (class "Default")
      (node (ref "E12") (pin "12") (pinfunction "Q5_12") (pintype "output"))
      (node (ref "E17") (pin "12") (pinfunction "2C2_12") (pintype "input"))
    )
    (net (code "68") (name "Net-(E12A-Q6)") (class "Default")
      (node (ref "E12") (pin "15") (pinfunction "Q6_15") (pintype "output"))
      (node (ref "E17") (pin "10") (pinfunction "2C0_10") (pintype "input"))
    )
    (net (code "69") (name "Net-(E13A-Q1)") (class "Default")
      (node (ref "E13") (pin "2") (pinfunction "Q1_2") (pintype "output"))
      (node (ref "E19") (pin "12") (pinfunction "2C2_12") (pintype "input"))
    )
    (net (code "70") (name "Net-(E13A-Q2)") (class "Default")
      (node (ref "E13") (pin "5") (pinfunction "Q2_5") (pintype "output"))
      (node (ref "E19") (pin "10") (pinfunction "2C0_10") (pintype "input"))
    )
    (net (code "71") (name "Net-(E13A-Q3)") (class "Default")
      (node (ref "E13") (pin "7") (pinfunction "Q3_7") (pintype "output"))
      (node (ref "E18") (pin "3") (pinfunction "1C3_3") (pintype "input"))
    )
    (net (code "72") (name "Net-(E13A-Q4)") (class "Default")
      (node (ref "E13") (pin "10") (pinfunction "Q4_10") (pintype "output"))
      (node (ref "E18") (pin "5") (pinfunction "1C1_5") (pintype "input"))
    )
    (net (code "73") (name "Net-(E13A-Q5)") (class "Default")
      (node (ref "E13") (pin "12") (pinfunction "Q5_12") (pintype "output"))
      (node (ref "E18") (pin "4") (pinfunction "1C2_4") (pintype "input"))
    )
    (net (code "74") (name "Net-(E13A-Q6)") (class "Default")
      (node (ref "E13") (pin "15") (pinfunction "Q6_15") (pintype "output"))
      (node (ref "E18") (pin "6") (pinfunction "1C0_6") (pintype "input"))
    )
    (net (code "75") (name "Net-(E14A-Q1)") (class "Default")
      (node (ref "E14") (pin "2") (pinfunction "Q1_2") (pintype "output"))
      (node (ref "E18") (pin "13") (pinfunction "2C3_13") (pintype "input"))
    )
    (net (code "76") (name "Net-(E14A-Q2)") (class "Default")
      (node (ref "E14") (pin "5") (pinfunction "Q2_5") (pintype "output"))
      (node (ref "E18") (pin "11") (pinfunction "2C1_11") (pintype "input"))
    )
    (net (code "77") (name "Net-(E14A-Q3)") (class "Default")
      (node (ref "E14") (pin "7") (pinfunction "Q3_7") (pintype "output"))
      (node (ref "E18") (pin "12") (pinfunction "2C2_12") (pintype "input"))
    )
    (net (code "78") (name "Net-(E14A-Q4)") (class "Default")
      (node (ref "E14") (pin "10") (pinfunction "Q4_10") (pintype "output"))
      (node (ref "E18") (pin "10") (pinfunction "2C0_10") (pintype "input"))
    )
    (net (code "79") (name "Net-(E14A-Q5)") (class "Default")
      (node (ref "E14") (pin "12") (pinfunction "Q5_12") (pintype "output"))
      (node (ref "E17") (pin "3") (pinfunction "1C3_3") (pintype "input"))
    )
    (net (code "80") (name "Net-(E14A-Q6)") (class "Default")
      (node (ref "E14") (pin "15") (pinfunction "Q6_15") (pintype "output"))
      (node (ref "E17") (pin "5") (pinfunction "1C1_5") (pintype "input"))
    )
    (net (code "81") (name "Net-(E15A-Q1)") (class "Default")
      (node (ref "E15") (pin "2") (pinfunction "Q1_2") (pintype "output"))
      (node (ref "E19") (pin "3") (pinfunction "1C3_3") (pintype "input"))
    )
    (net (code "82") (name "Net-(E15A-Q2)") (class "Default")
      (node (ref "E15") (pin "5") (pinfunction "Q2_5") (pintype "output"))
      (node (ref "E19") (pin "5") (pinfunction "1C1_5") (pintype "input"))
    )
    (net (code "83") (name "Net-(E15A-Q3)") (class "Default")
      (node (ref "E15") (pin "7") (pinfunction "Q3_7") (pintype "output"))
      (node (ref "E19") (pin "4") (pinfunction "1C2_4") (pintype "input"))
    )
    (net (code "84") (name "Net-(E15A-Q4)") (class "Default")
      (node (ref "E15") (pin "10") (pinfunction "Q4_10") (pintype "output"))
      (node (ref "E19") (pin "6") (pinfunction "1C0_6") (pintype "input"))
    )
    (net (code "85") (name "Net-(E15A-Q5)") (class "Default")
      (node (ref "E15") (pin "12") (pinfunction "Q5_12") (pintype "output"))
      (node (ref "E19") (pin "13") (pinfunction "2C3_13") (pintype "input"))
    )
    (net (code "86") (name "Net-(E15A-Q6)") (class "Default")
      (node (ref "E15") (pin "15") (pinfunction "Q6_15") (pintype "output"))
      (node (ref "E19") (pin "11") (pinfunction "2C1_11") (pintype "input"))
    )
    (net (code "87") (name "Net-(E16A-CLK)") (class "Default")
      (node (ref "E16") (pin "3") (pinfunction "CLK_3") (pintype "input"))
      (node (ref "E21") (pin "12") (pinfunction "O_12") (pintype "output"))
    )
    (net (code "88") (name "Net-(E20A-PRE)") (class "Default")
      (node (ref "E20") (pin "4") (pinfunction "PRE_4") (pintype "input"))
      (node (ref "E26") (pin "8") (pinfunction "~{Q4}_8") (pintype "output"))
    )
    (net (code "89") (name "Net-(E20B-CLK)") (class "Default")
      (node (ref "E20") (pin "11") (pinfunction "CLK_11") (pintype "input"))
      (node (ref "E22") (pin "1") (pinfunction "O_1") (pintype "output"))
      (node (ref "E4") (pin "9") (pinfunction "A_9") (pintype "input"))
    )
    (net (code "90") (name "Net-(E20B-Q)") (class "Default")
      (node (ref "E20") (pin "9") (pinfunction "Q_9") (pintype "output"))
      (node (ref "E22") (pin "11") (pinfunction "I0_11") (pintype "input"))
      (node (ref "E8") (pin "12") (pinfunction "I0_12") (pintype "input"))
    )
    (net (code "91") (name "Net-(E21A-I0)") (class "Default")
      (node (ref "E21") (pin "1") (pinfunction "I0_1") (pintype "input"))
      (node (ref "E24") (pin "4") (pinfunction "O_4") (pintype "output"))
    )
    (net (code "92") (name "Net-(E21B-I0)") (class "Default")
      (node (ref "E21") (pin "3") (pinfunction "I0_3") (pintype "input"))
      (node (ref "E21") (pin "4") (pinfunction "I1_4") (pintype "input"))
      (node (ref "E22") (pin "4") (pinfunction "O_4") (pintype "output"))
    )
    (net (code "93") (name "Net-(E21C-I2)") (class "Default")
      (node (ref "E21") (pin "11") (pinfunction "I2_11") (pintype "input"))
      (node (ref "E30") (pin "8") (pinfunction "O_8") (pintype "output"))
    )
    (net (code "94") (name "Net-(E21C-O)") (class "Default")
      (node (ref "E21") (pin "8") (pinfunction "O_8") (pintype "output"))
      (node (ref "E23") (pin "9") (pinfunction "I_9") (pintype "input"))
    )
    (net (code "95") (name "Net-(E22A-I0)") (class "Default")
      (node (ref "E22") (pin "2") (pinfunction "I0_2") (pintype "input"))
      (node (ref "E33") (pin "1") (pinfunction "O_1") (pintype "output"))
    )
    (net (code "96") (name "Net-(E22A-I1)") (class "Default")
      (node (ref "E22") (pin "3") (pinfunction "I1_3") (pintype "input"))
      (node (ref "E32") (pin "6") (pinfunction "O_6") (pintype "output"))
    )
    (net (code "97") (name "Net-(E22B-I0)") (class "Default")
      (node (ref "E22") (pin "5") (pinfunction "I0_5") (pintype "input"))
      (node (ref "E8") (pin "3") (pinfunction "O_3") (pintype "output"))
    )
    (net (code "98") (name "Net-(E22C-I0)") (class "Default")
      (node (ref "E22") (pin "8") (pinfunction "I0_8") (pintype "input"))
      (node (ref "E25") (pin "12") (pinfunction "O_12") (pintype "output"))
    )
    (net (code "99") (name "Net-(E22C-I1)") (class "Default")
      (node (ref "E22") (pin "9") (pinfunction "I1_9") (pintype "input"))
      (node (ref "E25") (pin "8") (pinfunction "O_8") (pintype "output"))
    )
    (net (code "100") (name "Net-(E22C-O)") (class "Default")
      (node (ref "E22") (pin "10") (pinfunction "O_10") (pintype "output"))
      (node (ref "E28") (pin "1") (pinfunction "1G_1") (pintype "input"))
      (node (ref "E28") (pin "15") (pinfunction "2G_15") (pintype "input"))
      (node (ref "E29") (pin "4") (pinfunction "G2A_4") (pintype "input"))
      (node (ref "E29") (pin "5") (pinfunction "G2B_5") (pintype "input"))
      (node (ref "E31") (pin "15") (pinfunction "2G_15") (pintype "input"))
    )
    (net (code "101") (name "Net-(E23A-I)") (class "Default")
      (node (ref "E23") (pin "1") (pinfunction "I_1") (pintype "input"))
      (node (ref "E33") (pin "4") (pinfunction "O_4") (pintype "output"))
    )
    (net (code "102") (name "Net-(E23E-I)") (class "Default")
      (node (ref "E23") (pin "11") (pinfunction "I_11") (pintype "input"))
      (node (ref "E24") (pin "10") (pinfunction "O_10") (pintype "output"))
    )
    (net (code "103") (name "Net-(E24D-O)") (class "Default")
      (node (ref "E24") (pin "8") (pinfunction "O_8") (pintype "output"))
      (node (ref "E32") (pin "5") (pinfunction "I1_5") (pintype "input"))
    )
    (net (code "104") (name "Net-(E24F-O)") (class "Default")
      (node (ref "E24") (pin "12") (pinfunction "O_12") (pintype "output"))
      (node (ref "E25") (pin "10") (pinfunction "I1_10") (pintype "input"))
      (node (ref "E33") (pin "6") (pinfunction "I1_6") (pintype "input"))
    )
    (net (code "105") (name "Net-(E25A-I0)") (class "Default")
      (node (ref "E25") (pin "1") (pinfunction "I0_1") (pintype "input"))
      (node (ref "E26") (pin "16") (pinfunction "Q1_16") (pintype "output"))
      (node (ref "E29") (pin "3") (pinfunction "C_3") (pintype "input"))
    )
    (net (code "106") (name "Net-(E25A-I2)") (class "Default")
      (node (ref "E25") (pin "13") (pinfunction "I2_13") (pintype "input"))
      (node (ref "E26") (pin "15") (pinfunction "Q2_15") (pintype "output"))
      (node (ref "E27") (pin "3") (pinfunction "I_3") (pintype "input"))
      (node (ref "E29") (pin "2") (pinfunction "B_2") (pintype "input"))
      (node (ref "E30") (pin "1") (pinfunction "I0_1") (pintype "input"))
    )
    (net (code "107") (name "Net-(E25C-I0)") (class "Default")
      (node (ref "E25") (pin "9") (pinfunction "I0_9") (pintype "input"))
      (node (ref "E26") (pin "9") (pinfunction "Q4_9") (pintype "output"))
    )
    (net (code "108") (name "Net-(E26A-Q3)") (class "Default")
      (node (ref "E26") (pin "10") (pinfunction "Q3_10") (pintype "output"))
      (node (ref "E29") (pin "1") (pinfunction "A_1") (pintype "input"))
    )
    (net (code "109") (name "Net-(E27A-O)") (class "Default")
      (node (ref "E27") (pin "2") (pinfunction "O_2") (pintype "output"))
      (node (ref "E30") (pin "12") (pinfunction "I0_12") (pintype "input"))
    )
    (net (code "110") (name "Net-(E27B-O)") (class "Default")
      (node (ref "E27") (pin "4") (pinfunction "O_4") (pintype "output"))
      (node (ref "E31") (pin "12") (pinfunction "2A1_12") (pintype "input"))
    )
    (net (code "111") (name "Net-(E27C-O)") (class "Default")
      (node (ref "E27") (pin "6") (pinfunction "O_6") (pintype "output"))
      (node (ref "E30") (pin "13") (pinfunction "I1_13") (pintype "input"))
    )
    (net (code "112") (name "Net-(E28A-1A1)") (class "Default")
      (node (ref "E28") (pin "2") (pinfunction "1A1_2") (pintype "input"))
      (node (ref "E29") (pin "9") (pinfunction "Y6_9") (pintype "output"))
      (node (ref "E32") (pin "2") (pinfunction "I1_2") (pintype "input"))
    )
    (net (code "113") (name "Net-(E28A-1A2)") (class "Default")
      (node (ref "E28") (pin "4") (pinfunction "1A2_4") (pintype "input"))
      (node (ref "E29") (pin "7") (pinfunction "Y7_7") (pintype "output"))
      (node (ref "E30") (pin "10") (pinfunction "I1_10") (pintype "input"))
      (node (ref "E32") (pin "1") (pinfunction "I0_1") (pintype "input"))
    )
    (net (code "114") (name "Net-(E28A-1A3)") (class "Default")
      (node (ref "E28") (pin "6") (pinfunction "1A3_6") (pintype "input"))
      (node (ref "E30") (pin "9") (pinfunction "I0_9") (pintype "input"))
      (node (ref "E31") (pin "6") (pinfunction "1A3_6") (pintype "input"))
      (node (ref "E32") (pin "8") (pinfunction "O_8") (pintype "output"))
      (node (ref "E33") (pin "5") (pinfunction "I0_5") (pintype "input"))
    )
    (net (code "115") (name "Net-(E28A-2A2)") (class "Default")
      (node (ref "E28") (pin "14") (pinfunction "2A2_14") (pintype "input"))
      (node (ref "E30") (pin "11") (pinfunction "O_11") (pintype "output"))
    )
    (net (code "116") (name "Net-(E29A-Y0)") (class "Default")
      (node (ref "E29") (pin "15") (pinfunction "Y0_15") (pintype "output"))
      (node (ref "E33") (pin "8") (pinfunction "I0_8") (pintype "input"))
    )
    (net (code "117") (name "Net-(E29A-Y1)") (class "Default")
      (node (ref "E29") (pin "14") (pinfunction "Y1_14") (pintype "output"))
      (node (ref "E33") (pin "12") (pinfunction "I1_12") (pintype "input"))
    )
    (net (code "118") (name "Net-(E29A-Y2)") (class "Default")
      (node (ref "E29") (pin "13") (pinfunction "Y2_13") (pintype "output"))
      (node (ref "E30") (pin "2") (pinfunction "I1_2") (pintype "input"))
      (node (ref "E32") (pin "10") (pinfunction "I1_10") (pintype "input"))
    )
    (net (code "119") (name "Net-(E29A-Y3)") (class "Default")
      (node (ref "E29") (pin "12") (pinfunction "Y3_12") (pintype "output"))
      (node (ref "E32") (pin "9") (pinfunction "I0_9") (pintype "input"))
    )
    (net (code "120") (name "Net-(E29A-Y4)") (class "Default")
      (node (ref "E29") (pin "11") (pinfunction "Y4_11") (pintype "output"))
      (node (ref "E31") (pin "10") (pinfunction "1A4_10") (pintype "input"))
    )
    (net (code "121") (name "Net-(E29A-Y5)") (class "Default")
      (node (ref "E29") (pin "10") (pinfunction "Y5_10") (pintype "output"))
      (node (ref "E31") (pin "2") (pinfunction "1A1_2") (pintype "input"))
    )
    (net (code "122") (name "Net-(E30A-O)") (class "Default")
      (node (ref "E30") (pin "3") (pinfunction "O_3") (pintype "output"))
      (node (ref "E31") (pin "14") (pinfunction "2A2_14") (pintype "input"))
    )
    (net (code "123") (name "Net-(E30B-O)") (class "Default")
      (node (ref "E30") (pin "6") (pinfunction "O_6") (pintype "output"))
      (node (ref "E34") (pin "1") (pinfunction "1G_1") (pintype "input"))
      (node (ref "E34") (pin "15") (pinfunction "2G_15") (pintype "input"))
      (node (ref "E35") (pin "4") (pinfunction "G2A_4") (pintype "input"))
      (node (ref "E35") (pin "5") (pinfunction "G2B_5") (pintype "input"))
    )
    (net (code "124") (name "Net-(E31A-1A2)") (class "Default")
      (node (ref "E31") (pin "4") (pinfunction "1A2_4") (pintype "input"))
      (node (ref "E32") (pin "3") (pinfunction "O_3") (pintype "output"))
    )
    (net (code "125") (name "Net-(E33C-O)") (class "Default")
      (node (ref "E33") (pin "10") (pinfunction "O_10") (pintype "output"))
      (node (ref "E36") (pin "9") (pinfunction "CLK_9") (pintype "input"))
    )
    (net (code "126") (name "Net-(E34A-1A3)") (class "Default")
      (node (ref "E34") (pin "6") (pinfunction "1A3_6") (pintype "input"))
      (node (ref "E35") (pin "9") (pinfunction "Y6_9") (pintype "output"))
    )
    (net (code "127") (name "Net-(E34A-2A1)") (class "Default")
      (node (ref "E34") (pin "12") (pinfunction "2A1_12") (pintype "input"))
      (node (ref "E35") (pin "10") (pinfunction "Y5_10") (pintype "output"))
    )
    (net (code "128") (name "POWCK") (class "Default")
      (node (ref "E24") (pin "11") (pinfunction "I_11") (pintype "input"))
      (node (ref "J2") (pin "28") (pinfunction "28_28") (pintype "passive"))
      (node (ref "R33") (pin "1") (pinfunction "1_1") (pintype "passive"))
    )
    (net (code "129") (name "THIS") (class "Default")
      (node (ref "E20") (pin "5") (pinfunction "Q_5") (pintype "output"))
      (node (ref "E28") (pin "12") (pinfunction "2A1_12") (pintype "input"))
    )
    (net (code "130") (name "VCC") (class "Default")
      (node (ref "C1") (pin "1") (pinfunction "1_1") (pintype "passive"))
      (node (ref "C10") (pin "1") (pinfunction "1_1") (pintype "passive"))
      (node (ref "C11") (pin "1") (pinfunction "1_1") (pintype "passive"))
      (node (ref "C12") (pin "1") (pinfunction "1_1") (pintype "passive"))
      (node (ref "C13") (pin "1") (pinfunction "1_1") (pintype "passive"))
      (node (ref "C14") (pin "1") (pinfunction "1_1") (pintype "passive"))
      (node (ref "C15") (pin "1") (pinfunction "1_1") (pintype "passive"))
      (node (ref "C16") (pin "1") (pinfunction "1_1") (pintype "passive"))
      (node (ref "C17") (pin "1") (pinfunction "1_1") (pintype "passive"))
      (node (ref "C18") (pin "1") (pinfunction "1_1") (pintype "passive"))
      (node (ref "C19") (pin "1") (pinfunction "1_1") (pintype "passive"))
      (node (ref "C2") (pin "1") (pinfunction "1_1") (pintype "passive"))
      (node (ref "C20") (pin "1") (pinfunction "1_1") (pintype "passive"))
      (node (ref "C21") (pin "1") (pinfunction "1_1") (pintype "passive"))
      (node (ref "C22") (pin "1") (pinfunction "1_1") (pintype "passive"))
      (node (ref "C23") (pin "1") (pinfunction "1_1") (pintype "passive"))
      (node (ref "C24") (pin "1") (pinfunction "1_1") (pintype "passive"))
      (node (ref "C25") (pin "1") (pinfunction "1_1") (pintype "passive"))
      (node (ref "C26") (pin "1") (pinfunction "1_1") (pintype "passive"))
      (node (ref "C27") (pin "1") (pinfunction "1_1") (pintype "passive"))
      (node (ref "C28") (pin "1") (pinfunction "1_1") (pintype "passive"))
      (node (ref "C29") (pin "1") (pinfunction "1_1") (pintype "passive"))
      (node (ref "C3") (pin "1") (pinfunction "1_1") (pintype "passive"))
      (node (ref "C30") (pin "1") (pinfunction "1_1") (pintype "passive"))
      (node (ref "C31") (pin "1") (pinfunction "1_1") (pintype "passive"))
      (node (ref "C32") (pin "1") (pinfunction "1_1") (pintype "passive"))
      (node (ref "C33") (pin "1") (pinfunction "1_1") (pintype "passive"))
      (node (ref "C34") (pin "1") (pinfunction "1_1") (pintype "passive"))
      (node (ref "C35") (pin "1") (pinfunction "1_1") (pintype "passive"))
      (node (ref "C36") (pin "1") (pinfunction "1_1") (pintype "passive"))
      (node (ref "C38") (pin "+") (pinfunction "+_+") (pintype "passive"))
      (node (ref "C39") (pin "+") (pinfunction "+_+") (pintype "passive"))
      (node (ref "C4") (pin "1") (pinfunction "1_1") (pintype "passive"))
      (node (ref "C5") (pin "1") (pinfunction "1_1") (pintype "passive"))
      (node (ref "C6") (pin "1") (pinfunction "1_1") (pintype "passive"))
      (node (ref "C7") (pin "1") (pinfunction "1_1") (pintype "passive"))
      (node (ref "C8") (pin "1") (pinfunction "1_1") (pintype "passive"))
      (node (ref "C9") (pin "1") (pinfunction "1_1") (pintype "passive"))
      (node (ref "E16") (pin "10") (pinfunction "PRE_10") (pintype "input"))
      (node (ref "E16") (pin "4") (pinfunction "PRE_4") (pintype "input"))
      (node (ref "E20") (pin "10") (pinfunction "PRE_10") (pintype "input"))
      (node (ref "E29") (pin "6") (pinfunction "G1_6") (pintype "input"))
      (node (ref "E34") (pin "10") (pinfunction "1A4_10") (pintype "input"))
      (node (ref "E35") (pin "6") (pinfunction "G1_6") (pintype "input"))
      (node (ref "E36") (pin "1") (pinfunction "CLR_1") (pintype "input"))
      (node (ref "E36") (pin "11") (pinfunction "D4_11") (pintype "input"))
      (node (ref "E36") (pin "13") (pinfunction "D5_13") (pintype "input"))
      (node (ref "E36") (pin "6") (pinfunction "D3_6") (pintype "input"))
      (node (ref "E4") (pin "10") (pinfunction "B_10") (pintype "input"))
      (node (ref "E4") (pin "11") (pinfunction "CLR_11") (pintype "input"))
      (node (ref "J3") (pin "16") (pinfunction "16_16") (pintype "passive"))
      (node (ref "J4") (pin "16") (pinfunction "16_16") (pintype "passive"))
      (node (ref "PAD7") (pin "1") (pinfunction "P_1") (pintype "passive"))
      (node (ref "R10") (pin "2") (pinfunction "2_2") (pintype "passive"))
      (node (ref "R11") (pin "2") (pinfunction "2_2") (pintype "passive"))
      (node (ref "R12") (pin "2") (pinfunction "2_2") (pintype "passive"))
      (node (ref "R13") (pin "2") (pinfunction "2_2") (pintype "passive"))
      (node (ref "R14") (pin "2") (pinfunction "2_2") (pintype "passive"))
      (node (ref "R15") (pin "2") (pinfunction "2_2") (pintype "passive"))
      (node (ref "R16") (pin "2") (pinfunction "2_2") (pintype "passive"))
      (node (ref "R25") (pin "1") (pinfunction "1_1") (pintype "passive"))
      (node (ref "R26") (pin "2") (pinfunction "2_2") (pintype "passive"))
      (node (ref "R28") (pin "2") (pinfunction "2_2") (pintype "passive"))
      (node (ref "R29") (pin "2") (pinfunction "2_2") (pintype "passive"))
      (node (ref "R31") (pin "2") (pinfunction "2_2") (pintype "passive"))
      (node (ref "R32") (pin "2") (pinfunction "2_2") (pintype "passive"))
      (node (ref "R33") (pin "2") (pinfunction "2_2") (pintype "passive"))
      (node (ref "R34") (pin "1") (pinfunction "1_1") (pintype "passive"))
      (node (ref "R35") (pin "1") (pinfunction "1_1") (pintype "passive"))
      (node (ref "R36") (pin "1") (pinfunction "1_1") (pintype "passive"))
      (node (ref "R5") (pin "2") (pinfunction "2_2") (pintype "passive"))
      (node (ref "R6") (pin "2") (pinfunction "2_2") (pintype "passive"))
      (node (ref "R7") (pin "2") (pinfunction "2_2") (pintype "passive"))
      (node (ref "R8") (pin "2") (pinfunction "2_2") (pintype "passive"))
      (node (ref "R9") (pin "2") (pinfunction "2_2") (pintype "passive"))
    )
    (net (code "131") (name "unconnected-(E4B-~{Q}-Pad12)") (class "Default")
      (node (ref "E4") (pin "12") (pinfunction "~{Q}_12") (pintype "output"))
    )
    (net (code "132") (name "unconnected-(E5A-~{Q1}-Pad3)") (class "Default")
      (node (ref "E5") (pin "3") (pinfunction "~{Q1}_3") (pintype "output"))
    )
    (net (code "133") (name "unconnected-(E5A-~{Q2}-Pad6)") (class "Default")
      (node (ref "E5") (pin "6") (pinfunction "~{Q2}_6") (pintype "output"))
    )
    (net (code "134") (name "unconnected-(E5A-~{Q3}-Pad11)") (class "Default")
      (node (ref "E5") (pin "11") (pinfunction "~{Q3}_11") (pintype "output"))
    )
    (net (code "135") (name "unconnected-(E5A-~{Q4}-Pad14)") (class "Default")
      (node (ref "E5") (pin "14") (pinfunction "~{Q4}_14") (pintype "output"))
    )
    (net (code "136") (name "unconnected-(E6A-~{Q1}-Pad3)") (class "Default")
      (node (ref "E6") (pin "3") (pinfunction "~{Q1}_3") (pintype "output"))
    )
    (net (code "137") (name "unconnected-(E6A-~{Q2}-Pad6)") (class "Default")
      (node (ref "E6") (pin "6") (pinfunction "~{Q2}_6") (pintype "output"))
    )
    (net (code "138") (name "unconnected-(E6A-~{Q3}-Pad11)") (class "Default")
      (node (ref "E6") (pin "11") (pinfunction "~{Q3}_11") (pintype "output"))
    )
    (net (code "139") (name "unconnected-(E6A-~{Q4}-Pad14)") (class "Default")
      (node (ref "E6") (pin "14") (pinfunction "~{Q4}_14") (pintype "output"))
    )
    (net (code "140") (name "unconnected-(E7A-~{Q1}-Pad3)") (class "Default")
      (node (ref "E7") (pin "3") (pinfunction "~{Q1}_3") (pintype "output"))
    )
    (net (code "141") (name "unconnected-(E7A-~{Q2}-Pad6)") (class "Default")
      (node (ref "E7") (pin "6") (pinfunction "~{Q2}_6") (pintype "output"))
    )
    (net (code "142") (name "unconnected-(E7A-~{Q3}-Pad11)") (class "Default")
      (node (ref "E7") (pin "11") (pinfunction "~{Q3}_11") (pintype "output"))
    )
    (net (code "143") (name "unconnected-(E7A-~{Q4}-Pad14)") (class "Default")
      (node (ref "E7") (pin "14") (pinfunction "~{Q4}_14") (pintype "output"))
    )
    (net (code "144") (name "unconnected-(E16A-Q-Pad5)") (class "Default")
      (node (ref "E16") (pin "5") (pinfunction "Q_5") (pintype "output"))
    )
    (net (code "145") (name "unconnected-(E20A-~{Q}-Pad6)") (class "Default")
      (node (ref "E20") (pin "6") (pinfunction "~{Q}_6") (pintype "output"))
    )
    (net (code "146") (name "unconnected-(E26A-~{Q1}-Pad1)") (class "Default")
      (node (ref "E26") (pin "1") (pinfunction "~{Q1}_1") (pintype "output"))
    )
    (net (code "147") (name "unconnected-(E26A-~{Q2}-Pad14)") (class "Default")
      (node (ref "E26") (pin "14") (pinfunction "~{Q2}_14") (pintype "output"))
    )
    (net (code "148") (name "unconnected-(E26A-~{Q3}-Pad11)") (class "Default")
      (node (ref "E26") (pin "11") (pinfunction "~{Q3}_11") (pintype "output"))
    )
    (net (code "149") (name "unconnected-(E34A-1Y4-Pad9)") (class "Default")
      (node (ref "E34") (pin "9") (pinfunction "1Y4_9") (pintype "tri_state"))
    )
    (net (code "150") (name "unconnected-(E35A-Y0-Pad15)") (class "Default")
      (node (ref "E35") (pin "15") (pinfunction "Y0_15") (pintype "output"))
    )
    (net (code "151") (name "unconnected-(E35A-Y1-Pad14)") (class "Default")
      (node (ref "E35") (pin "14") (pinfunction "Y1_14") (pintype "output"))
    )
    (net (code "152") (name "unconnected-(E35A-Y2-Pad13)") (class "Default")
      (node (ref "E35") (pin "13") (pinfunction "Y2_13") (pintype "output"))
    )
    (net (code "153") (name "unconnected-(E35A-Y3-Pad12)") (class "Default")
      (node (ref "E35") (pin "12") (pinfunction "Y3_12") (pintype "output"))
    )
    (net (code "154") (name "unconnected-(E35A-Y7-Pad7)") (class "Default")
      (node (ref "E35") (pin "7") (pinfunction "Y7_7") (pintype "output"))
    )
    (net (code "155") (name "unconnected-(E36A-Q3-Pad7)") (class "Default")
      (node (ref "E36") (pin "7") (pinfunction "Q3_7") (pintype "output"))
    )
    (net (code "156") (name "unconnected-(E36A-Q4-Pad10)") (class "Default")
      (node (ref "E36") (pin "10") (pinfunction "Q4_10") (pintype "output"))
    )
    (net (code "157") (name "unconnected-(E36A-Q5-Pad12)") (class "Default")
      (node (ref "E36") (pin "12") (pinfunction "Q5_12") (pintype "output"))
    )
    (net (code "158") (name "unconnected-(J1-Pad2)") (class "Default")
      (node (ref "J1") (pin "2") (pinfunction "2_2") (pintype "passive"))
    )
    (net (code "159") (name "unconnected-(J1-Pad4)") (class "Default")
      (node (ref "J1") (pin "4") (pinfunction "4_4") (pintype "passive"))
    )
    (net (code "160") (name "~{ADRLTH}") (class "Default")
      (node (ref "E12") (pin "9") (pinfunction "CLK_9") (pintype "input"))
      (node (ref "E14") (pin "9") (pinfunction "CLK_9") (pintype "input"))
      (node (ref "E8") (pin "11") (pinfunction "O_11") (pintype "output"))
    )
    (net (code "161") (name "~{BFSW}") (class "Default")
      (node (ref "E28") (pin "9") (pinfunction "1Y4_9") (pintype "tri_state"))
      (node (ref "J2") (pin "24") (pinfunction "24_24") (pintype "passive"))
    )
    (net (code "162") (name "~{BKDTACNTL}") (class "Default")
      (node (ref "E28") (pin "3") (pinfunction "1Y1_3") (pintype "tri_state"))
      (node (ref "J2") (pin "12") (pinfunction "12_12") (pintype "passive"))
    )
    (net (code "163") (name "~{BOOTF}") (class "Default")
      (node (ref "E16") (pin "2") (pinfunction "D_2") (pintype "input"))
      (node (ref "E16") (pin "6") (pinfunction "~{Q}_6") (pintype "output"))
      (node (ref "E28") (pin "10") (pinfunction "1A4_10") (pintype "input"))
    )
    (net (code "164") (name "~{BUSEN}") (class "Default")
      (node (ref "E34") (pin "13") (pinfunction "2Y2_13") (pintype "tri_state"))
      (node (ref "J1") (pin "24") (pinfunction "24_24") (pintype "passive"))
    )
    (net (code "165") (name "~{DEP}") (class "Default")
      (node (ref "E28") (pin "5") (pinfunction "1Y2_5") (pintype "tri_state"))
      (node (ref "J2") (pin "20") (pinfunction "20_20") (pintype "passive"))
    )
    (net (code "166") (name "~{DSPLTH}") (class "Default")
      (node (ref "E13") (pin "9") (pinfunction "CLK_9") (pintype "input"))
      (node (ref "E15") (pin "9") (pinfunction "CLK_9") (pintype "input"))
      (node (ref "E8") (pin "8") (pinfunction "O_8") (pintype "output"))
    )
    (net (code "167") (name "~{E35-Y4}") (class "Default")
      (node (ref "E31") (pin "1") (pinfunction "1G_1") (pintype "input"))
      (node (ref "E32") (pin "12") (pinfunction "I0_12") (pintype "input"))
      (node (ref "E35") (pin "11") (pinfunction "Y4_11") (pintype "output"))
    )
    (net (code "168") (name "~{EMA0}") (class "Default")
      (node (ref "E27") (pin "11") (pinfunction "I_11") (pintype "input"))
      (node (ref "J1") (pin "30") (pinfunction "30_30") (pintype "passive"))
      (node (ref "R34") (pin "2") (pinfunction "2_2") (pintype "passive"))
    )
    (net (code "169") (name "~{EMA1}") (class "Default")
      (node (ref "E27") (pin "9") (pinfunction "I_9") (pintype "input"))
      (node (ref "J1") (pin "28") (pinfunction "28_28") (pintype "passive"))
      (node (ref "R35") (pin "2") (pinfunction "2_2") (pintype "passive"))
    )
    (net (code "170") (name "~{EMA2}") (class "Default")
      (node (ref "E27") (pin "13") (pinfunction "I_13") (pintype "input"))
      (node (ref "J1") (pin "32") (pinfunction "32_32") (pintype "passive"))
      (node (ref "R36") (pin "2") (pinfunction "2_2") (pintype "passive"))
    )
    (net (code "171") (name "~{EMODE}") (class "Default")
      (node (ref "E1") (pin "6") (pinfunction "MOD_6") (pintype "input"))
      (node (ref "E16") (pin "8") (pinfunction "~{Q}_8") (pintype "output"))
      (node (ref "E2") (pin "6") (pinfunction "MOD_6") (pintype "input"))
      (node (ref "E22") (pin "6") (pinfunction "I1_6") (pintype "input"))
      (node (ref "E3") (pin "6") (pinfunction "MOD_6") (pintype "input"))
    )
    (net (code "172") (name "~{EXTPUL}") (class "Default")
      (node (ref "J4") (pin "9") (pinfunction "9_9") (pintype "passive"))
    )
    (net (code "173") (name "~{FUN}") (class "Default")
      (node (ref "E21") (pin "5") (pinfunction "I2_5") (pintype "input"))
      (node (ref "E24") (pin "3") (pinfunction "I_3") (pintype "input"))
      (node (ref "E25") (pin "11") (pinfunction "I2_11") (pintype "input"))
      (node (ref "E25") (pin "2") (pinfunction "I1_2") (pintype "input"))
      (node (ref "J4") (pin "15") (pinfunction "15_15") (pintype "passive"))
    )
    (net (code "174") (name "~{GATEENT}") (class "Default")
      (node (ref "E10") (pin "19") (pinfunction "G_19") (pintype "input"))
      (node (ref "E11") (pin "19") (pinfunction "G_19") (pintype "input"))
      (node (ref "E21") (pin "6") (pinfunction "O_6") (pintype "output"))
      (node (ref "E30") (pin "4") (pinfunction "I0_4") (pintype "input"))
      (node (ref "E9") (pin "19") (pinfunction "G_19") (pintype "input"))
    )
    (net (code "175") (name "~{GATESR}") (class "Default")
      (node (ref "E10") (pin "1") (pinfunction "G_1") (pintype "input"))
      (node (ref "E11") (pin "1") (pinfunction "G_1") (pintype "input"))
      (node (ref "E32") (pin "11") (pinfunction "O_11") (pintype "output"))
      (node (ref "E9") (pin "1") (pinfunction "G_1") (pintype "input"))
    )
    (net (code "176") (name "~{IND1}") (class "Default")
      (node (ref "E28") (pin "7") (pinfunction "1Y3_7") (pintype "tri_state"))
      (node (ref "E34") (pin "3") (pinfunction "1Y1_3") (pintype "tri_state"))
      (node (ref "J2") (pin "8") (pinfunction "8_8") (pintype "passive"))
    )
    (net (code "177") (name "~{IND2}") (class "Default")
      (node (ref "E34") (pin "5") (pinfunction "1Y2_5") (pintype "tri_state"))
      (node (ref "J2") (pin "4") (pinfunction "4_4") (pintype "passive"))
    )
    (net (code "178") (name "~{INIT}") (class "Default")
      (node (ref "E31") (pin "9") (pinfunction "1Y4_9") (pintype "tri_state"))
      (node (ref "J2") (pin "34") (pinfunction "34_34") (pintype "passive"))
    )
    (net (code "179") (name "~{KEY-F}") (class "Default")
      (node (ref "E26") (pin "13") (pinfunction "C12_13") (pintype "input"))
      (node (ref "E26") (pin "4") (pinfunction "C34_4") (pintype "input"))
      (node (ref "E27") (pin "5") (pinfunction "I_5") (pintype "input"))
      (node (ref "J4") (pin "3") (pinfunction "3_3") (pintype "passive"))
    )
    (net (code "180") (name "~{KEYCNTL}") (class "Default")
      (node (ref "E31") (pin "13") (pinfunction "2Y2_13") (pintype "tri_state"))
      (node (ref "J2") (pin "10") (pinfunction "10_10") (pintype "passive"))
    )
    (net (code "181") (name "~{KEYSTB}") (class "Default")
      (node (ref "E16") (pin "11") (pinfunction "CLK_11") (pintype "input"))
      (node (ref "E21") (pin "13") (pinfunction "I2_13") (pintype "input"))
      (node (ref "E24") (pin "2") (pinfunction "O_2") (pintype "output"))
      (node (ref "E33") (pin "11") (pinfunction "I0_11") (pintype "input"))
      (node (ref "E33") (pin "9") (pinfunction "I1_9") (pintype "input"))
    )
    (net (code "182") (name "~{KFUN0}") (class "Default")
      (node (ref "E26") (pin "2") (pinfunction "D1_2") (pintype "input"))
      (node (ref "E3") (pin "1") (pinfunction "SER_1") (pintype "input"))
      (node (ref "E3") (pin "2") (pinfunction "A_2") (pintype "input"))
      (node (ref "J3") (pin "3") (pinfunction "3_3") (pintype "passive"))
    )
    (net (code "183") (name "~{KFUN1}") (class "Default")
      (node (ref "E2") (pin "1") (pinfunction "SER_1") (pintype "input"))
      (node (ref "E2") (pin "2") (pinfunction "A_2") (pintype "input"))
      (node (ref "E26") (pin "3") (pinfunction "D2_3") (pintype "input"))
      (node (ref "J3") (pin "2") (pinfunction "2_2") (pintype "passive"))
    )
    (net (code "184") (name "~{KFUN2}") (class "Default")
      (node (ref "E1") (pin "1") (pinfunction "SER_1") (pintype "input"))
      (node (ref "E1") (pin "2") (pinfunction "A_2") (pintype "input"))
      (node (ref "E26") (pin "6") (pinfunction "D3_6") (pintype "input"))
      (node (ref "J3") (pin "1") (pinfunction "1_1") (pintype "passive"))
    )
    (net (code "185") (name "~{LAENAB}") (class "Default")
      (node (ref "E23") (pin "2") (pinfunction "O_2") (pintype "open_collector"))
      (node (ref "J2") (pin "22") (pinfunction "22_22") (pintype "passive"))
    )
    (net (code "186") (name "~{MAEN}") (class "Default")
      (node (ref "E23") (pin "8") (pinfunction "O_8") (pintype "open_collector"))
      (node (ref "J2") (pin "32") (pinfunction "32_32") (pintype "passive"))
    )
    (net (code "187") (name "~{MALC}") (class "Default")
      (node (ref "E28") (pin "11") (pinfunction "2Y1_11") (pintype "tri_state"))
      (node (ref "J2") (pin "36") (pinfunction "36_36") (pintype "passive"))
    )
    (net (code "188") (name "~{MCLOCK}") (class "Default")
      (node (ref "E33") (pin "2") (pinfunction "I0_2") (pintype "input"))
      (node (ref "J4") (pin "1") (pinfunction "1_1") (pintype "passive"))
    )
    (net (code "189") (name "~{MD}") (class "Default")
      (node (ref "E34") (pin "7") (pinfunction "1Y3_7") (pintype "tri_state"))
      (node (ref "J2") (pin "18") (pinfunction "18_18") (pintype "passive"))
    )
    (net (code "190") (name "~{MEMSTART}") (class "Default")
      (node (ref "E31") (pin "3") (pinfunction "1Y1_3") (pintype "tri_state"))
      (node (ref "E31") (pin "5") (pinfunction "1Y2_5") (pintype "tri_state"))
      (node (ref "J2") (pin "26") (pinfunction "26_26") (pintype "passive"))
    )
    (net (code "191") (name "~{MH0}") (class "Default")
      (node (ref "E20") (pin "12") (pinfunction "D_12") (pintype "input"))
      (node (ref "E20") (pin "8") (pinfunction "~{Q}_8") (pintype "output"))
      (node (ref "E21") (pin "10") (pinfunction "I1_10") (pintype "input"))
      (node (ref "E8") (pin "10") (pinfunction "I1_10") (pintype "input"))
      (node (ref "E8") (pin "2") (pinfunction "I1_2") (pintype "input"))
    )
    (net (code "192") (name "~{MSIRDIS}") (class "Default")
      (node (ref "E31") (pin "11") (pinfunction "2Y1_11") (pintype "tri_state"))
      (node (ref "J2") (pin "2") (pinfunction "2_2") (pintype "passive"))
    )
    (net (code "193") (name "~{PANLOCK}") (class "Default")
      (node (ref "E24") (pin "13") (pinfunction "I_13") (pintype "input"))
      (node (ref "J2") (pin "6") (pinfunction "6_6") (pintype "passive"))
      (node (ref "R31") (pin "1") (pinfunction "1_1") (pintype "passive"))
    )
    (net (code "194") (name "~{PULSELOADADD}") (class "Default")
      (node (ref "E31") (pin "7") (pinfunction "1Y3_7") (pintype "tri_state"))
      (node (ref "J2") (pin "40") (pinfunction "40_40") (pintype "passive"))
    )
    (net (code "195") (name "~{RUN}") (class "Default")
      (node (ref "E24") (pin "5") (pinfunction "I_5") (pintype "input"))
      (node (ref "J1") (pin "18") (pinfunction "18_18") (pintype "passive"))
      (node (ref "R28") (pin "1") (pinfunction "1_1") (pintype "passive"))
    )
    (net (code "196") (name "~{SHLT}") (class "Default")
      (node (ref "E27") (pin "1") (pinfunction "I_1") (pintype "input"))
      (node (ref "J3") (pin "5") (pinfunction "5_5") (pintype "passive"))
    )
    (net (code "197") (name "~{SINGSTEP}") (class "Default")
      (node (ref "E28") (pin "13") (pinfunction "2Y2_13") (pintype "tri_state"))
      (node (ref "J2") (pin "14") (pinfunction "14_14") (pintype "passive"))
    )
    (net (code "198") (name "~{SRDATA}") (class "Default")
      (node (ref "E32") (pin "13") (pinfunction "I1_13") (pintype "input"))
      (node (ref "E8") (pin "1") (pinfunction "I0_1") (pintype "input"))
      (node (ref "J2") (pin "30") (pinfunction "30_30") (pintype "passive"))
      (node (ref "R29") (pin "1") (pinfunction "1_1") (pintype "passive"))
      (node (ref "R30") (pin "2") (pinfunction "2_2") (pintype "passive"))
    )
    (net (code "199") (name "~{STATE}") (class "Default")
      (node (ref "E34") (pin "11") (pinfunction "2Y1_11") (pintype "tri_state"))
      (node (ref "J2") (pin "38") (pinfunction "38_38") (pintype "passive"))
    )
    (net (code "200") (name "~{STHIS}") (class "Default")
      (node (ref "E20") (pin "2") (pinfunction "D_2") (pintype "input"))
      (node (ref "J3") (pin "4") (pinfunction "4_4") (pintype "passive"))
    )
    (net (code "201") (name "~{TSI}") (class "Default")
      (node (ref "E20") (pin "3") (pinfunction "CLK_3") (pintype "input"))
      (node (ref "E21") (pin "9") (pinfunction "I0_9") (pintype "input"))
      (node (ref "E24") (pin "9") (pinfunction "I_9") (pintype "input"))
      (node (ref "J1") (pin "26") (pinfunction "26_26") (pintype "passive"))
      (node (ref "R26") (pin "1") (pinfunction "1_1") (pintype "passive"))
      (node (ref "R27") (pin "2") (pinfunction "2_2") (pintype "passive"))
    )
  )
)
